# AP.net
KiCad netlist of a schematic drawn in Altium Designer
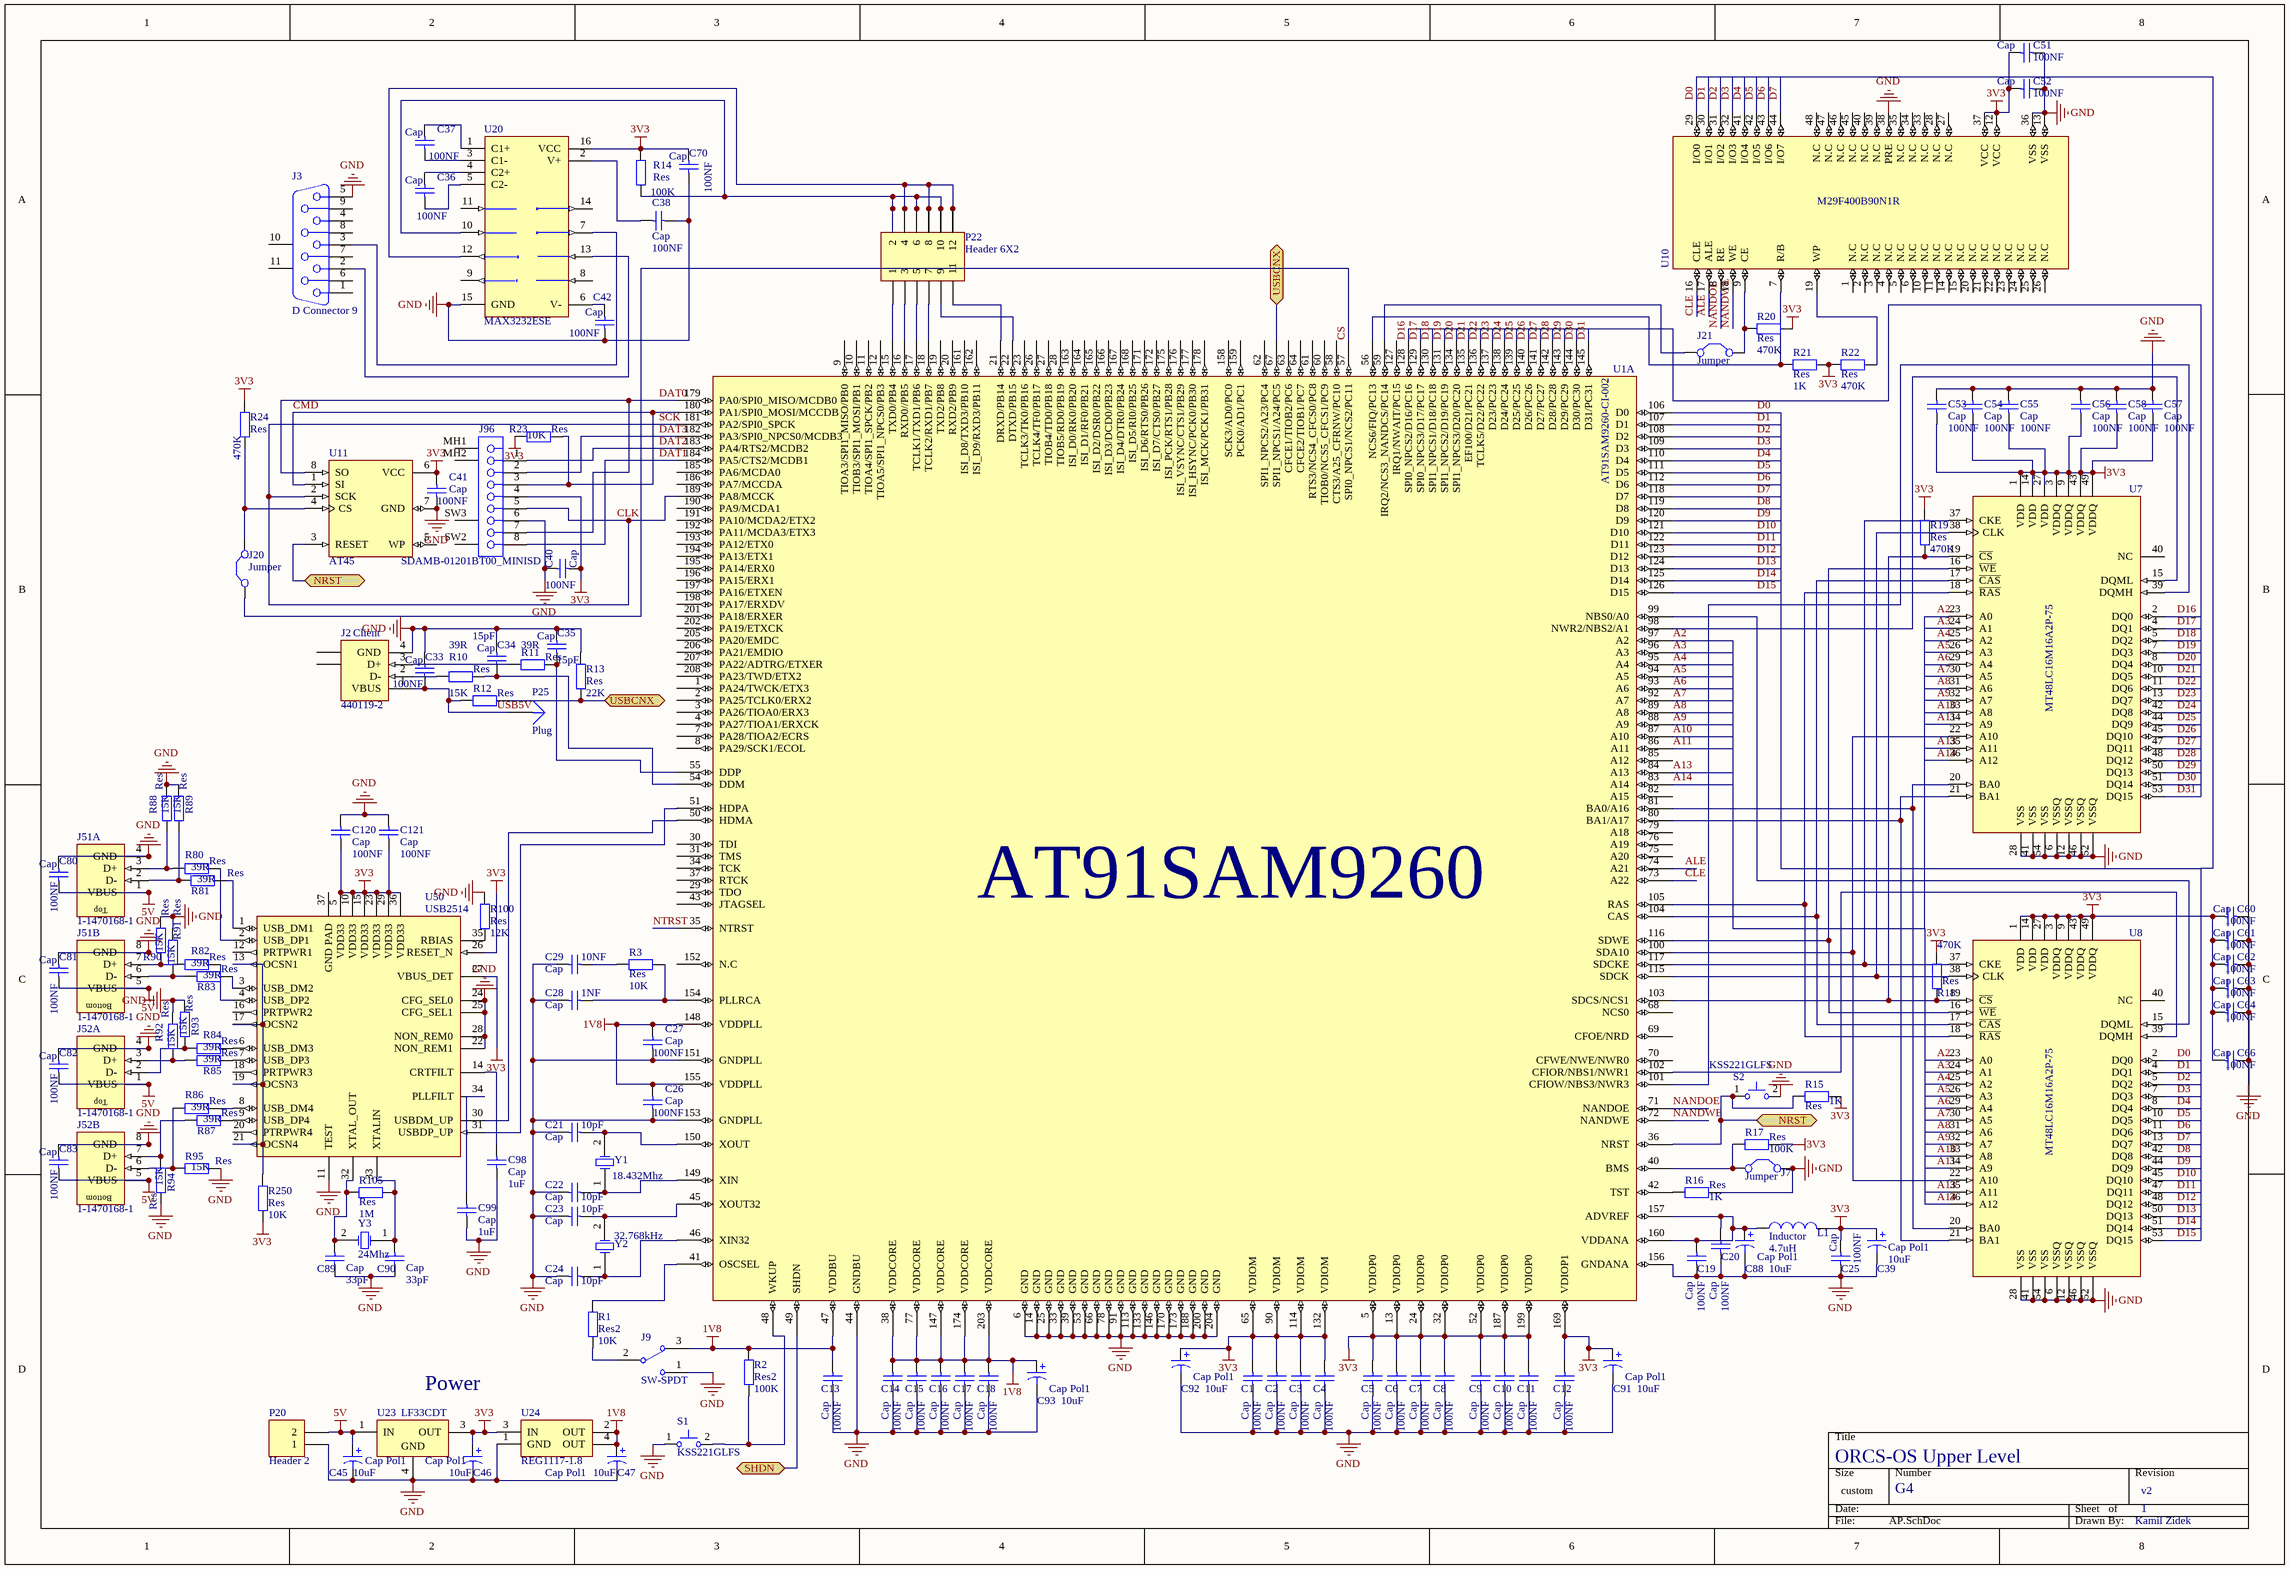
[diagram p0: AP.SchDoc]

(export (version "E")
  (design (tool "Eeschema 10.0.6"))
  (components
    (comp (ref "C1")
      (value "Cap")
      (footprint "C0805")
      (description "Capacitor (Semiconductor SIM Model)")
      (fields (field (name "ALTIUM_VALUE") "100NF") (field (name "PUBLISHER") "Altium Limited"))
      (libsource (lib "Miscellaneous Devices") (part "Cap Semi"))
    )
    (comp (ref "C2")
      (value "Cap")
      (footprint "C0805")
      (description "Capacitor (Semiconductor SIM Model)")
      (fields (field (name "ALTIUM_VALUE") "100NF") (field (name "PUBLISHER") "Altium Limited"))
      (libsource (lib "Miscellaneous Devices") (part "Cap Semi"))
    )
    (comp (ref "C3")
      (value "Cap")
      (footprint "C0805")
      (description "Capacitor (Semiconductor SIM Model)")
      (fields (field (name "ALTIUM_VALUE") "100NF") (field (name "PUBLISHER") "Altium Limited"))
      (libsource (lib "Miscellaneous Devices") (part "Cap Semi"))
    )
    (comp (ref "C4")
      (value "Cap")
      (footprint "C0805")
      (description "Capacitor (Semiconductor SIM Model)")
      (fields (field (name "ALTIUM_VALUE") "100NF") (field (name "PUBLISHER") "Altium Limited"))
      (libsource (lib "Miscellaneous Devices") (part "Cap Semi"))
    )
    (comp (ref "C5")
      (value "Cap")
      (footprint "C0805")
      (description "Capacitor (Semiconductor SIM Model)")
      (fields (field (name "ALTIUM_VALUE") "100NF") (field (name "PUBLISHER") "Altium Limited"))
      (libsource (lib "Miscellaneous Devices") (part "Cap Semi"))
    )
    (comp (ref "C6")
      (value "Cap")
      (footprint "C0805")
      (description "Capacitor (Semiconductor SIM Model)")
      (fields (field (name "ALTIUM_VALUE") "100NF") (field (name "PUBLISHER") "Altium Limited"))
      (libsource (lib "Miscellaneous Devices") (part "Cap Semi"))
    )
    (comp (ref "C7")
      (value "Cap")
      (footprint "C0805")
      (description "Capacitor (Semiconductor SIM Model)")
      (fields (field (name "ALTIUM_VALUE") "100NF") (field (name "PUBLISHER") "Altium Limited"))
      (libsource (lib "Miscellaneous Devices") (part "Cap Semi"))
    )
    (comp (ref "C8")
      (value "Cap")
      (footprint "C0805")
      (description "Capacitor (Semiconductor SIM Model)")
      (fields (field (name "ALTIUM_VALUE") "100NF") (field (name "PUBLISHER") "Altium Limited"))
      (libsource (lib "Miscellaneous Devices") (part "Cap Semi"))
    )
    (comp (ref "C9")
      (value "Cap")
      (footprint "C0805")
      (description "Capacitor (Semiconductor SIM Model)")
      (fields (field (name "ALTIUM_VALUE") "100NF") (field (name "PUBLISHER") "Altium Limited"))
      (libsource (lib "Miscellaneous Devices") (part "Cap Semi"))
    )
    (comp (ref "C10")
      (value "Cap")
      (footprint "C0805")
      (description "Capacitor (Semiconductor SIM Model)")
      (fields (field (name "ALTIUM_VALUE") "100NF") (field (name "PUBLISHER") "Altium Limited"))
      (libsource (lib "Miscellaneous Devices") (part "Cap Semi"))
    )
    (comp (ref "C11")
      (value "Cap")
      (footprint "C0805")
      (description "Capacitor (Semiconductor SIM Model)")
      (fields (field (name "ALTIUM_VALUE") "100NF") (field (name "PUBLISHER") "Altium Limited"))
      (libsource (lib "Miscellaneous Devices") (part "Cap Semi"))
    )
    (comp (ref "C12")
      (value "Cap")
      (footprint "C0805")
      (description "Capacitor (Semiconductor SIM Model)")
      (fields (field (name "ALTIUM_VALUE") "100NF") (field (name "PUBLISHER") "Altium Limited"))
      (libsource (lib "Miscellaneous Devices") (part "Cap Semi"))
    )
    (comp (ref "C13")
      (value "Cap")
      (footprint "C0805")
      (description "Capacitor (Semiconductor SIM Model)")
      (fields (field (name "ALTIUM_VALUE") "100NF") (field (name "PUBLISHER") "Altium Limited"))
      (libsource (lib "Miscellaneous Devices") (part "Cap Semi"))
    )
    (comp (ref "C14")
      (value "Cap")
      (footprint "C0805")
      (description "Capacitor (Semiconductor SIM Model)")
      (fields (field (name "ALTIUM_VALUE") "100NF") (field (name "PUBLISHER") "Altium Limited"))
      (libsource (lib "Miscellaneous Devices") (part "Cap Semi"))
    )
    (comp (ref "C15")
      (value "Cap")
      (footprint "C0805")
      (description "Capacitor (Semiconductor SIM Model)")
      (fields (field (name "ALTIUM_VALUE") "100NF") (field (name "PUBLISHER") "Altium Limited"))
      (libsource (lib "Miscellaneous Devices") (part "Cap Semi"))
    )
    (comp (ref "C16")
      (value "Cap")
      (footprint "C0805")
      (description "Capacitor (Semiconductor SIM Model)")
      (fields (field (name "ALTIUM_VALUE") "100NF") (field (name "PUBLISHER") "Altium Limited"))
      (libsource (lib "Miscellaneous Devices") (part "Cap Semi"))
    )
    (comp (ref "C17")
      (value "Cap")
      (footprint "C0805")
      (description "Capacitor (Semiconductor SIM Model)")
      (fields (field (name "ALTIUM_VALUE") "100NF") (field (name "PUBLISHER") "Altium Limited"))
      (libsource (lib "Miscellaneous Devices") (part "Cap Semi"))
    )
    (comp (ref "C18")
      (value "Cap")
      (footprint "C0805")
      (description "Capacitor (Semiconductor SIM Model)")
      (fields (field (name "ALTIUM_VALUE") "100NF") (field (name "PUBLISHER") "Altium Limited"))
      (libsource (lib "Miscellaneous Devices") (part "Cap Semi"))
    )
    (comp (ref "C19")
      (value "Cap")
      (footprint "C0805")
      (description "Capacitor (Semiconductor SIM Model)")
      (fields (field (name "ALTIUM_VALUE") "100NF") (field (name "PUBLISHER") "Altium Limited"))
      (libsource (lib "Miscellaneous Devices") (part "Cap Semi"))
    )
    (comp (ref "C20")
      (value "Cap")
      (footprint "C0805")
      (description "Capacitor (Semiconductor SIM Model)")
      (fields (field (name "ALTIUM_VALUE") "100NF") (field (name "PUBLISHER") "Altium Limited"))
      (libsource (lib "Miscellaneous Devices") (part "Cap Semi"))
    )
    (comp (ref "C21")
      (value "Cap")
      (footprint "C0805")
      (description "Capacitor (Semiconductor SIM Model)")
      (fields (field (name "ALTIUM_VALUE") "10pF") (field (name "PUBLISHER") "Altium Limited"))
      (libsource (lib "Miscellaneous Devices") (part "Cap Semi"))
    )
    (comp (ref "C22")
      (value "Cap")
      (footprint "C0805")
      (description "Capacitor (Semiconductor SIM Model)")
      (fields (field (name "ALTIUM_VALUE") "10pF") (field (name "PUBLISHER") "Altium Limited"))
      (libsource (lib "Miscellaneous Devices") (part "Cap Semi"))
    )
    (comp (ref "C23")
      (value "Cap")
      (footprint "C0805")
      (description "Capacitor (Semiconductor SIM Model)")
      (fields (field (name "ALTIUM_VALUE") "10pF") (field (name "PUBLISHER") "Altium Limited"))
      (libsource (lib "Miscellaneous Devices") (part "Cap Semi"))
    )
    (comp (ref "C24")
      (value "Cap")
      (footprint "C0805")
      (description "Capacitor (Semiconductor SIM Model)")
      (fields (field (name "ALTIUM_VALUE") "10pF") (field (name "PUBLISHER") "Altium Limited"))
      (libsource (lib "Miscellaneous Devices") (part "Cap Semi"))
    )
    (comp (ref "C25")
      (value "Cap")
      (footprint "C0805")
      (description "Capacitor (Semiconductor SIM Model)")
      (fields (field (name "ALTIUM_VALUE") "100NF") (field (name "PUBLISHER") "Altium Limited"))
      (libsource (lib "Miscellaneous Devices") (part "Cap Semi"))
    )
    (comp (ref "C26")
      (value "Cap")
      (footprint "C0805")
      (description "Capacitor (Semiconductor SIM Model)")
      (fields (field (name "ALTIUM_VALUE") "100NF") (field (name "PUBLISHER") "Altium Limited"))
      (libsource (lib "Miscellaneous Devices") (part "Cap Semi"))
    )
    (comp (ref "C27")
      (value "Cap")
      (footprint "C0805")
      (description "Capacitor (Semiconductor SIM Model)")
      (fields (field (name "ALTIUM_VALUE") "100NF") (field (name "PUBLISHER") "Altium Limited"))
      (libsource (lib "Miscellaneous Devices") (part "Cap Semi"))
    )
    (comp (ref "C28")
      (value "Cap")
      (footprint "C0805")
      (description "Capacitor (Semiconductor SIM Model)")
      (fields (field (name "ALTIUM_VALUE") "1NF") (field (name "PUBLISHER") "Altium Limited"))
      (libsource (lib "Miscellaneous Devices") (part "Cap Semi"))
    )
    (comp (ref "C29")
      (value "Cap")
      (footprint "C0805")
      (description "Capacitor (Semiconductor SIM Model)")
      (fields (field (name "ALTIUM_VALUE") "10NF") (field (name "PUBLISHER") "Altium Limited"))
      (libsource (lib "Miscellaneous Devices") (part "Cap Semi"))
    )
    (comp (ref "C33")
      (value "Cap")
      (footprint "C0805")
      (description "Capacitor (Semiconductor SIM Model)")
      (fields (field (name "ALTIUM_VALUE") "100NF") (field (name "PUBLISHER") "Altium Limited"))
      (libsource (lib "Miscellaneous Devices") (part "Cap Semi"))
    )
    (comp (ref "C34")
      (value "Cap")
      (footprint "C0805")
      (description "Capacitor (Semiconductor SIM Model)")
      (fields (field (name "ALTIUM_VALUE") "15pF") (field (name "PUBLISHER") "Altium Limited"))
      (libsource (lib "Miscellaneous Devices") (part "Cap Semi"))
    )
    (comp (ref "C35")
      (value "Cap")
      (footprint "C0805")
      (description "Capacitor (Semiconductor SIM Model)")
      (fields (field (name "ALTIUM_VALUE") "15pF") (field (name "PUBLISHER") "Altium Limited"))
      (libsource (lib "Miscellaneous Devices") (part "Cap Semi"))
    )
    (comp (ref "C36")
      (value "Cap")
      (footprint "C0805")
      (description "Capacitor (Semiconductor SIM Model)")
      (fields (field (name "ALTIUM_VALUE") "100NF") (field (name "PUBLISHER") "Altium Limited"))
      (libsource (lib "Miscellaneous Devices") (part "Cap Semi"))
    )
    (comp (ref "C37")
      (value "Cap")
      (footprint "C0805")
      (description "Capacitor (Semiconductor SIM Model)")
      (fields (field (name "ALTIUM_VALUE") "100NF") (field (name "PUBLISHER") "Altium Limited"))
      (libsource (lib "Miscellaneous Devices") (part "Cap Semi"))
    )
    (comp (ref "C38")
      (value "Cap")
      (footprint "C0805")
      (description "Capacitor (Semiconductor SIM Model)")
      (fields (field (name "ALTIUM_VALUE") "100NF") (field (name "PUBLISHER") "Altium Limited"))
      (libsource (lib "Miscellaneous Devices") (part "Cap Semi"))
    )
    (comp (ref "C39")
      (value "Cap Pol1")
      (footprint "Miscellaneous Devices:A")
      (description "Polarized Capacitor (Radial)")
      (fields (field (name "ALTIUM_VALUE") "10uF") (field (name "PUBLISHER") "Altium Limited"))
      (libsource (lib "Miscellaneous Devices") (part "Cap Pol1"))
    )
    (comp (ref "C40")
      (value "Cap")
      (footprint "C0805")
      (description "Capacitor (Semiconductor SIM Model)")
      (fields (field (name "ALTIUM_VALUE") "100NF") (field (name "PUBLISHER") "Altium Limited"))
      (libsource (lib "Miscellaneous Devices") (part "Cap Semi"))
    )
    (comp (ref "C41")
      (value "Cap")
      (footprint "C0805")
      (description "Capacitor (Semiconductor SIM Model)")
      (fields (field (name "ALTIUM_VALUE") "100NF") (field (name "PUBLISHER") "Altium Limited"))
      (libsource (lib "Miscellaneous Devices") (part "Cap Semi"))
    )
    (comp (ref "C42")
      (value "Cap")
      (footprint "C0805")
      (description "Capacitor (Semiconductor SIM Model)")
      (fields (field (name "ALTIUM_VALUE") "100NF") (field (name "PUBLISHER") "Altium Limited"))
      (libsource (lib "Miscellaneous Devices") (part "Cap Semi"))
    )
    (comp (ref "C45")
      (value "Cap Pol1")
      (footprint "Miscellaneous Devices:A")
      (description "Polarized Capacitor (Radial)")
      (fields (field (name "ALTIUM_VALUE") "10uF") (field (name "PUBLISHER") "Altium Limited"))
      (libsource (lib "Miscellaneous Devices") (part "Cap Pol1"))
    )
    (comp (ref "C46")
      (value "Cap Pol1")
      (footprint "Miscellaneous Devices:A")
      (description "Polarized Capacitor (Radial)")
      (fields (field (name "ALTIUM_VALUE") "10uF") (field (name "PUBLISHER") "Altium Limited"))
      (libsource (lib "Miscellaneous Devices") (part "Cap Pol1"))
    )
    (comp (ref "C47")
      (value "Cap Pol1")
      (footprint "Miscellaneous Devices:A")
      (description "Polarized Capacitor (Radial)")
      (fields (field (name "ALTIUM_VALUE") "10uF") (field (name "PUBLISHER") "Altium Limited"))
      (libsource (lib "Miscellaneous Devices") (part "Cap Pol1"))
    )
    (comp (ref "C51")
      (value "Cap")
      (footprint "C0805")
      (description "Capacitor (Semiconductor SIM Model)")
      (fields (field (name "ALTIUM_VALUE") "100NF") (field (name "PUBLISHER") "Altium Limited"))
      (libsource (lib "Miscellaneous Devices") (part "Cap Semi"))
    )
    (comp (ref "C52")
      (value "Cap")
      (footprint "C0805")
      (description "Capacitor (Semiconductor SIM Model)")
      (fields (field (name "ALTIUM_VALUE") "100NF") (field (name "PUBLISHER") "Altium Limited"))
      (libsource (lib "Miscellaneous Devices") (part "Cap Semi"))
    )
    (comp (ref "C53")
      (value "Cap")
      (footprint "C0805")
      (description "Capacitor (Semiconductor SIM Model)")
      (fields (field (name "ALTIUM_VALUE") "100NF") (field (name "PUBLISHER") "Altium Limited"))
      (libsource (lib "Miscellaneous Devices") (part "Cap Semi"))
    )
    (comp (ref "C54")
      (value "Cap")
      (footprint "C0805")
      (description "Capacitor (Semiconductor SIM Model)")
      (fields (field (name "ALTIUM_VALUE") "100NF") (field (name "PUBLISHER") "Altium Limited"))
      (libsource (lib "Miscellaneous Devices") (part "Cap Semi"))
    )
    (comp (ref "C55")
      (value "Cap")
      (footprint "C0805")
      (description "Capacitor (Semiconductor SIM Model)")
      (fields (field (name "ALTIUM_VALUE") "100NF") (field (name "PUBLISHER") "Altium Limited"))
      (libsource (lib "Miscellaneous Devices") (part "Cap Semi"))
    )
    (comp (ref "C56")
      (value "Cap")
      (footprint "C0805")
      (description "Capacitor (Semiconductor SIM Model)")
      (fields (field (name "ALTIUM_VALUE") "100NF") (field (name "PUBLISHER") "Altium Limited"))
      (libsource (lib "Miscellaneous Devices") (part "Cap Semi"))
    )
    (comp (ref "C57")
      (value "Cap")
      (footprint "C0805")
      (description "Capacitor (Semiconductor SIM Model)")
      (fields (field (name "ALTIUM_VALUE") "100NF") (field (name "PUBLISHER") "Altium Limited"))
      (libsource (lib "Miscellaneous Devices") (part "Cap Semi"))
    )
    (comp (ref "C58")
      (value "Cap")
      (footprint "C0805")
      (description "Capacitor (Semiconductor SIM Model)")
      (fields (field (name "ALTIUM_VALUE") "100NF") (field (name "PUBLISHER") "Altium Limited"))
      (libsource (lib "Miscellaneous Devices") (part "Cap Semi"))
    )
    (comp (ref "C60")
      (value "Cap")
      (footprint "C0805")
      (description "Capacitor (Semiconductor SIM Model)")
      (fields (field (name "ALTIUM_VALUE") "100NF") (field (name "PUBLISHER") "Altium Limited"))
      (libsource (lib "Miscellaneous Devices") (part "Cap Semi"))
    )
    (comp (ref "C61")
      (value "Cap")
      (footprint "C0805")
      (description "Capacitor (Semiconductor SIM Model)")
      (fields (field (name "ALTIUM_VALUE") "100NF") (field (name "PUBLISHER") "Altium Limited"))
      (libsource (lib "Miscellaneous Devices") (part "Cap Semi"))
    )
    (comp (ref "C62")
      (value "Cap")
      (footprint "C0805")
      (description "Capacitor (Semiconductor SIM Model)")
      (fields (field (name "ALTIUM_VALUE") "100NF") (field (name "PUBLISHER") "Altium Limited"))
      (libsource (lib "Miscellaneous Devices") (part "Cap Semi"))
    )
    (comp (ref "C63")
      (value "Cap")
      (footprint "C0805")
      (description "Capacitor (Semiconductor SIM Model)")
      (fields (field (name "ALTIUM_VALUE") "100NF") (field (name "PUBLISHER") "Altium Limited"))
      (libsource (lib "Miscellaneous Devices") (part "Cap Semi"))
    )
    (comp (ref "C64")
      (value "Cap")
      (footprint "C0805")
      (description "Capacitor (Semiconductor SIM Model)")
      (fields (field (name "ALTIUM_VALUE") "100NF") (field (name "PUBLISHER") "Altium Limited"))
      (libsource (lib "Miscellaneous Devices") (part "Cap Semi"))
    )
    (comp (ref "C66")
      (value "Cap")
      (footprint "C0805")
      (description "Capacitor (Semiconductor SIM Model)")
      (fields (field (name "ALTIUM_VALUE") "100NF") (field (name "PUBLISHER") "Altium Limited"))
      (libsource (lib "Miscellaneous Devices") (part "Cap Semi"))
    )
    (comp (ref "C70")
      (value "Cap")
      (footprint "C0805")
      (description "Capacitor (Semiconductor SIM Model)")
      (fields (field (name "ALTIUM_VALUE") "100NF") (field (name "PUBLISHER") "Altium Limited"))
      (libsource (lib "Miscellaneous Devices") (part "Cap Semi"))
    )
    (comp (ref "C80")
      (value "Cap")
      (footprint "C0805")
      (description "Capacitor (Semiconductor SIM Model)")
      (fields (field (name "ALTIUM_VALUE") "100NF") (field (name "PUBLISHER") "Altium Limited"))
      (libsource (lib "Miscellaneous Devices") (part "Cap Semi"))
    )
    (comp (ref "C81")
      (value "Cap")
      (footprint "C0805")
      (description "Capacitor (Semiconductor SIM Model)")
      (fields (field (name "ALTIUM_VALUE") "100NF") (field (name "PUBLISHER") "Altium Limited"))
      (libsource (lib "Miscellaneous Devices") (part "Cap Semi"))
    )
    (comp (ref "C82")
      (value "Cap")
      (footprint "C0805")
      (description "Capacitor (Semiconductor SIM Model)")
      (fields (field (name "ALTIUM_VALUE") "100NF") (field (name "PUBLISHER") "Altium Limited"))
      (libsource (lib "Miscellaneous Devices") (part "Cap Semi"))
    )
    (comp (ref "C83")
      (value "Cap")
      (footprint "C0805")
      (description "Capacitor (Semiconductor SIM Model)")
      (fields (field (name "ALTIUM_VALUE") "100NF") (field (name "PUBLISHER") "Altium Limited"))
      (libsource (lib "Miscellaneous Devices") (part "Cap Semi"))
    )
    (comp (ref "C88")
      (value "Cap Pol1")
      (footprint "Miscellaneous Devices:A")
      (description "Polarized Capacitor (Radial)")
      (fields (field (name "ALTIUM_VALUE") "10uF") (field (name "PUBLISHER") "Altium Limited"))
      (libsource (lib "Miscellaneous Devices") (part "Cap Pol1"))
    )
    (comp (ref "C89")
      (value "Cap")
      (footprint "C0805")
      (description "Capacitor (Semiconductor SIM Model)")
      (fields (field (name "ALTIUM_VALUE") "33pF") (field (name "PUBLISHER") "Altium Limited"))
      (libsource (lib "Miscellaneous Devices") (part "Cap Semi"))
    )
    (comp (ref "C90")
      (value "Cap")
      (footprint "C0805")
      (description "Capacitor (Semiconductor SIM Model)")
      (fields (field (name "ALTIUM_VALUE") "33pF") (field (name "PUBLISHER") "Altium Limited"))
      (libsource (lib "Miscellaneous Devices") (part "Cap Semi"))
    )
    (comp (ref "C91")
      (value "Cap Pol1")
      (footprint "Miscellaneous Devices:A")
      (description "Polarized Capacitor (Radial)")
      (fields (field (name "ALTIUM_VALUE") "10uF") (field (name "PUBLISHER") "Altium Limited"))
      (libsource (lib "Miscellaneous Devices") (part "Cap Pol1"))
    )
    (comp (ref "C92")
      (value "Cap Pol1")
      (footprint "Miscellaneous Devices:A")
      (description "Polarized Capacitor (Radial)")
      (fields (field (name "ALTIUM_VALUE") "10uF") (field (name "PUBLISHER") "Altium Limited"))
      (libsource (lib "Miscellaneous Devices") (part "Cap Pol1"))
    )
    (comp (ref "C93")
      (value "Cap Pol1")
      (footprint "Miscellaneous Devices:A")
      (description "Polarized Capacitor (Radial)")
      (fields (field (name "ALTIUM_VALUE") "10uF") (field (name "PUBLISHER") "Altium Limited"))
      (libsource (lib "Miscellaneous Devices") (part "Cap Pol1"))
    )
    (comp (ref "C98")
      (value "Cap")
      (footprint "C0805")
      (description "Capacitor (Semiconductor SIM Model)")
      (fields (field (name "ALTIUM_VALUE") "1uF") (field (name "PUBLISHER") "Altium Limited"))
      (libsource (lib "Miscellaneous Devices") (part "Cap Semi"))
    )
    (comp (ref "C99")
      (value "Cap")
      (footprint "C0805")
      (description "Capacitor (Semiconductor SIM Model)")
      (fields (field (name "ALTIUM_VALUE") "1uF") (field (name "PUBLISHER") "Altium Limited"))
      (libsource (lib "Miscellaneous Devices") (part "Cap Semi"))
    )
    (comp (ref "C120")
      (value "Cap")
      (footprint "C0805")
      (description "Capacitor (Semiconductor SIM Model)")
      (fields (field (name "ALTIUM_VALUE") "100NF") (field (name "PUBLISHER") "Altium Limited"))
      (libsource (lib "Miscellaneous Devices") (part "Cap Semi"))
    )
    (comp (ref "C121")
      (value "Cap")
      (footprint "C0805")
      (description "Capacitor (Semiconductor SIM Model)")
      (fields (field (name "ALTIUM_VALUE") "100NF") (field (name "PUBLISHER") "Altium Limited"))
      (libsource (lib "Miscellaneous Devices") (part "Cap Semi"))
    )
    (comp (ref "J2")
      (value "440119-2")
      (footprint "440247")
      (description "USB 1.1, Right Angle, Thru-Hole, B Type, Receptacle, 4 Position, Black")
      (fields (field (name "PUBLISHER") "Altium Limited"))
      (libsource (lib "AMP Serial Bus USB") (part "440119-2"))
    )
    (comp (ref "J3")
      (value "D Connector 9")
      (footprint "DSUB1.385-2H9")
      (description "Receptacle Assembly, 9 Position, Right Angle")
      (fields (field (name "PUBLISHER") "Altium Limited"))
      (libsource (lib "Miscellaneous Connectors") (part "D Connector 9"))
    )
    (comp (ref "J7")
      (value "Jumper")
      (footprint "RAD-0.2")
      (description "Jumper Wire")
      (fields (field (name "PUBLISHER") "Altium Limited"))
      (libsource (lib "Miscellaneous Devices") (part "Jumper"))
    )
    (comp (ref "J9")
      (value "SW-SPDT")
      (footprint "TL36WW15050")
      (description "SPDT Subminiature Toggle Switch, Right Angle Mounting, Vertical Actuation")
      (fields (field (name "PUBLISHER") "Altium Limited"))
      (libsource (lib "Miscellaneous Devices") (part "SW-SPDT"))
    )
    (comp (ref "J20")
      (value "Jumper")
      (footprint "RAD-0.2")
      (description "Jumper Wire")
      (fields (field (name "PUBLISHER") "Altium Limited"))
      (libsource (lib "Miscellaneous Devices") (part "Jumper"))
    )
    (comp (ref "J21")
      (value "Jumper")
      (footprint "RAD-0.2")
      (description "Jumper Wire")
      (fields (field (name "PUBLISHER") "Altium Limited"))
      (libsource (lib "Miscellaneous Devices") (part "Jumper"))
    )
    (comp (ref "J51")
      (value "1-1470168-1")
      (footprint "1470168")
      (description "USB 1.1, Right Angle, Thru-Hole, A Type, Receptacle, 4x4 Position, Stacked, Black")
      (fields (field (name "PUBLISHER") "Altium Limited"))
      (libsource (lib "AMP Serial Bus USB") (part "1-1470168-1"))
    )
    (comp (ref "J52")
      (value "1-1470168-1")
      (footprint "1470168")
      (description "USB 1.1, Right Angle, Thru-Hole, A Type, Receptacle, 4x4 Position, Stacked, Black")
      (fields (field (name "PUBLISHER") "Altium Limited"))
      (libsource (lib "AMP Serial Bus USB") (part "1-1470168-1"))
    )
    (comp (ref "J96")
      (value "SDAMB-01201BT00_MINISD")
      (footprint "Kingfont Card Secure Digital:SDAMB-012_miniSD")
      (description "Secure Digital Card Connector, Type A without Cover; Surface Mount; 9-Position, 1u\" Au Plating")
      (fields (field (name "PUBLISHER") "Altium Limited"))
      (libsource (lib "Kingfont Secure Digital Card_miniSD") (part "SDAMB-01201BT00_MINISD"))
    )
    (comp (ref "L1")
      (value "Inductor")
      (footprint "0402-A")
      (fields (field (name "ALTIUM_VALUE") "4.7uH") (field (name "PUBLISHER") "Altium Limited"))
      (libsource (lib "Miscellaneous Devices") (part "Inductor"))
    )
    (comp (ref "P20")
      (value "Header 2")
      (footprint "HDR1X2")
      (description "Header, 2-Pin")
      (fields (field (name "PUBLISHER") "Altium Limited"))
      (libsource (lib "Miscellaneous Connectors") (part "Header 2"))
    )
    (comp (ref "P22")
      (value "Header 6X2")
      (footprint "HDR2X6")
      (description "Header, 6-Pin, Dual row")
      (fields (field (name "PUBLISHER") "Altium Limited"))
      (libsource (lib "Miscellaneous Connectors") (part "Header 6X2"))
    )
    (comp (ref "P25")
      (value "Plug")
      (footprint "PIN1")
      (fields (field (name "PUBLISHER") "Altium Limited"))
      (libsource (lib "Miscellaneous Connectors") (part "Plug"))
    )
    (comp (ref "R1")
      (value "Res2")
      (footprint "Miscellaneous Devices:2012[0805]")
      (description "Resistor")
      (fields (field (name "ALTIUM_VALUE") "10K") (field (name "PUBLISHER") "Altium Limited"))
      (libsource (lib "") (part "Res2_2"))
    )
    (comp (ref "R2")
      (value "Res2")
      (footprint "Miscellaneous Devices:2012[0805]")
      (description "Resistor")
      (fields (field (name "ALTIUM_VALUE") "100K") (field (name "PUBLISHER") "Altium Limited"))
      (libsource (lib "") (part "Res2_2"))
    )
    (comp (ref "R3")
      (value "Res")
      (footprint "Miscellaneous Devices:2012[0805]")
      (description "Resistor")
      (fields (field (name "ALTIUM_VALUE") "10K") (field (name "PUBLISHER") "Altium Limited"))
      (libsource (lib "Miscellaneous Devices") (part "Res2"))
    )
    (comp (ref "R10")
      (value "Res")
      (footprint "Miscellaneous Devices:2012[0805]")
      (description "Resistor")
      (fields (field (name "ALTIUM_VALUE") "39R") (field (name "PUBLISHER") "Altium Limited"))
      (libsource (lib "Miscellaneous Devices") (part "Res2"))
    )
    (comp (ref "R11")
      (value "Res")
      (footprint "Miscellaneous Devices:2012[0805]")
      (description "Resistor")
      (fields (field (name "ALTIUM_VALUE") "39R") (field (name "PUBLISHER") "Altium Limited"))
      (libsource (lib "Miscellaneous Devices") (part "Res2"))
    )
    (comp (ref "R12")
      (value "Res")
      (footprint "Miscellaneous Devices:2012[0805]")
      (description "Resistor")
      (fields (field (name "ALTIUM_VALUE") "15K") (field (name "PUBLISHER") "Altium Limited"))
      (libsource (lib "Miscellaneous Devices") (part "Res2"))
    )
    (comp (ref "R13")
      (value "Res")
      (footprint "Miscellaneous Devices:2012[0805]")
      (description "Resistor")
      (fields (field (name "ALTIUM_VALUE") "22K") (field (name "PUBLISHER") "Altium Limited"))
      (libsource (lib "") (part "Res2_2"))
    )
    (comp (ref "R14")
      (value "Res")
      (footprint "Miscellaneous Devices:2012[0805]")
      (description "Resistor")
      (fields (field (name "ALTIUM_VALUE") "100K") (field (name "PUBLISHER") "Altium Limited"))
      (libsource (lib "") (part "Res2_2"))
    )
    (comp (ref "R15")
      (value "Res")
      (footprint "Miscellaneous Devices:2012[0805]")
      (description "Resistor")
      (fields (field (name "ALTIUM_VALUE") "1K") (field (name "PUBLISHER") "Altium Limited"))
      (libsource (lib "Miscellaneous Devices") (part "Res2"))
    )
    (comp (ref "R16")
      (value "Res")
      (footprint "Miscellaneous Devices:2012[0805]")
      (description "Resistor")
      (fields (field (name "ALTIUM_VALUE") "1K") (field (name "PUBLISHER") "Altium Limited"))
      (libsource (lib "Miscellaneous Devices") (part "Res2"))
    )
    (comp (ref "R17")
      (value "Res")
      (footprint "Miscellaneous Devices:2012[0805]")
      (description "Resistor")
      (fields (field (name "ALTIUM_VALUE") "100K") (field (name "PUBLISHER") "Altium Limited"))
      (libsource (lib "Miscellaneous Devices") (part "Res2"))
    )
    (comp (ref "R18")
      (value "Res")
      (footprint "Miscellaneous Devices:2012[0805]")
      (description "Resistor")
      (fields (field (name "ALTIUM_VALUE") "470K") (field (name "PUBLISHER") "Altium Limited"))
      (libsource (lib "") (part "Res2_1"))
    )
    (comp (ref "R19")
      (value "Res")
      (footprint "Miscellaneous Devices:2012[0805]")
      (description "Resistor")
      (fields (field (name "ALTIUM_VALUE") "470K") (field (name "PUBLISHER") "Altium Limited"))
      (libsource (lib "") (part "Res2_1"))
    )
    (comp (ref "R20")
      (value "Res")
      (footprint "Miscellaneous Devices:2012[0805]")
      (description "Resistor")
      (fields (field (name "ALTIUM_VALUE") "470K") (field (name "PUBLISHER") "Altium Limited"))
      (libsource (lib "") (part "Res2_3"))
    )
    (comp (ref "R21")
      (value "Res")
      (footprint "Miscellaneous Devices:2012[0805]")
      (description "Resistor")
      (fields (field (name "ALTIUM_VALUE") "1K") (field (name "PUBLISHER") "Altium Limited"))
      (libsource (lib "") (part "Res2_3"))
    )
    (comp (ref "R22")
      (value "Res")
      (footprint "Miscellaneous Devices:2012[0805]")
      (description "Resistor")
      (fields (field (name "ALTIUM_VALUE") "470K") (field (name "PUBLISHER") "Altium Limited"))
      (libsource (lib "") (part "Res2_3"))
    )
    (comp (ref "R23")
      (value "Res")
      (footprint "Miscellaneous Devices:2012[0805]")
      (description "Resistor")
      (fields (field (name "ALTIUM_VALUE") "10K") (field (name "PUBLISHER") "Altium Limited"))
      (libsource (lib "Miscellaneous Devices") (part "Res2"))
    )
    (comp (ref "R24")
      (value "Res")
      (footprint "Miscellaneous Devices:2012[0805]")
      (description "Resistor")
      (fields (field (name "ALTIUM_VALUE") "470K") (field (name "PUBLISHER") "Altium Limited"))
      (libsource (lib "") (part "Res2_1"))
    )
    (comp (ref "R80")
      (value "Res")
      (footprint "Miscellaneous Devices:2012[0805]")
      (description "Resistor")
      (fields (field (name "ALTIUM_VALUE") "39R") (field (name "PUBLISHER") "Altium Limited"))
      (libsource (lib "Miscellaneous Devices") (part "Res2"))
    )
    (comp (ref "R81")
      (value "Res")
      (footprint "Miscellaneous Devices:2012[0805]")
      (description "Resistor")
      (fields (field (name "ALTIUM_VALUE") "39R") (field (name "PUBLISHER") "Altium Limited"))
      (libsource (lib "Miscellaneous Devices") (part "Res2"))
    )
    (comp (ref "R82")
      (value "Res")
      (footprint "Miscellaneous Devices:2012[0805]")
      (description "Resistor")
      (fields (field (name "ALTIUM_VALUE") "39R") (field (name "PUBLISHER") "Altium Limited"))
      (libsource (lib "Miscellaneous Devices") (part "Res2"))
    )
    (comp (ref "R83")
      (value "Res")
      (footprint "Miscellaneous Devices:2012[0805]")
      (description "Resistor")
      (fields (field (name "ALTIUM_VALUE") "39R") (field (name "PUBLISHER") "Altium Limited"))
      (libsource (lib "Miscellaneous Devices") (part "Res2"))
    )
    (comp (ref "R84")
      (value "Res")
      (footprint "Miscellaneous Devices:2012[0805]")
      (description "Resistor")
      (fields (field (name "ALTIUM_VALUE") "39R") (field (name "PUBLISHER") "Altium Limited"))
      (libsource (lib "Miscellaneous Devices") (part "Res2"))
    )
    (comp (ref "R85")
      (value "Res")
      (footprint "Miscellaneous Devices:2012[0805]")
      (description "Resistor")
      (fields (field (name "ALTIUM_VALUE") "39R") (field (name "PUBLISHER") "Altium Limited"))
      (libsource (lib "Miscellaneous Devices") (part "Res2"))
    )
    (comp (ref "R86")
      (value "Res")
      (footprint "Miscellaneous Devices:2012[0805]")
      (description "Resistor")
      (fields (field (name "ALTIUM_VALUE") "39R") (field (name "PUBLISHER") "Altium Limited"))
      (libsource (lib "Miscellaneous Devices") (part "Res2"))
    )
    (comp (ref "R87")
      (value "Res")
      (footprint "Miscellaneous Devices:2012[0805]")
      (description "Resistor")
      (fields (field (name "ALTIUM_VALUE") "39R") (field (name "PUBLISHER") "Altium Limited"))
      (libsource (lib "Miscellaneous Devices") (part "Res2"))
    )
    (comp (ref "R88")
      (value "Res")
      (footprint "Miscellaneous Devices:2012[0805]")
      (description "Resistor")
      (fields (field (name "ALTIUM_VALUE") "15K") (field (name "PUBLISHER") "Altium Limited"))
      (libsource (lib "") (part "Res2_2"))
    )
    (comp (ref "R89")
      (value "Res")
      (footprint "Miscellaneous Devices:2012[0805]")
      (description "Resistor")
      (fields (field (name "ALTIUM_VALUE") "15K") (field (name "PUBLISHER") "Altium Limited"))
      (libsource (lib "") (part "Res2_1"))
    )
    (comp (ref "R90")
      (value "Res")
      (footprint "Miscellaneous Devices:2012[0805]")
      (description "Resistor")
      (fields (field (name "ALTIUM_VALUE") "15K") (field (name "PUBLISHER") "Altium Limited"))
      (libsource (lib "") (part "Res2_2"))
    )
    (comp (ref "R91")
      (value "Res")
      (footprint "Miscellaneous Devices:2012[0805]")
      (description "Resistor")
      (fields (field (name "ALTIUM_VALUE") "15K") (field (name "PUBLISHER") "Altium Limited"))
      (libsource (lib "") (part "Res2_2"))
    )
    (comp (ref "R92")
      (value "Res")
      (footprint "Miscellaneous Devices:2012[0805]")
      (description "Resistor")
      (fields (field (name "ALTIUM_VALUE") "15K") (field (name "PUBLISHER") "Altium Limited"))
      (libsource (lib "") (part "Res2_2"))
    )
    (comp (ref "R93")
      (value "Res")
      (footprint "Miscellaneous Devices:2012[0805]")
      (description "Resistor")
      (fields (field (name "ALTIUM_VALUE") "15K") (field (name "PUBLISHER") "Altium Limited"))
      (libsource (lib "") (part "Res2_2"))
    )
    (comp (ref "R94")
      (value "Res")
      (footprint "Miscellaneous Devices:2012[0805]")
      (description "Resistor")
      (fields (field (name "ALTIUM_VALUE") "15K") (field (name "PUBLISHER") "Altium Limited"))
      (libsource (lib "") (part "Res2_2"))
    )
    (comp (ref "R95")
      (value "Res")
      (footprint "Miscellaneous Devices:2012[0805]")
      (description "Resistor")
      (fields (field (name "ALTIUM_VALUE") "15K") (field (name "PUBLISHER") "Altium Limited"))
      (libsource (lib "Miscellaneous Devices") (part "Res2"))
    )
    (comp (ref "R100")
      (value "Res")
      (footprint "Miscellaneous Devices:2012[0805]")
      (description "Resistor")
      (fields (field (name "ALTIUM_VALUE") "12K") (field (name "PUBLISHER") "Altium Limited"))
      (libsource (lib "") (part "Res2_2"))
    )
    (comp (ref "R105")
      (value "Res")
      (footprint "Miscellaneous Devices:2012[0805]")
      (description "Resistor")
      (fields (field (name "ALTIUM_VALUE") "1M") (field (name "PUBLISHER") "Altium Limited"))
      (libsource (lib "Miscellaneous Devices") (part "Res2"))
    )
    (comp (ref "R250")
      (value "Res")
      (footprint "Miscellaneous Devices:2012[0805]")
      (description "Resistor")
      (fields (field (name "ALTIUM_VALUE") "10K") (field (name "PUBLISHER") "Altium Limited"))
      (libsource (lib "") (part "Res2_1"))
    )
    (comp (ref "S1")
      (value "KSS221GLFS")
      (footprint "KSS-2G")
      (fields (field (name "PUBLISHER") "Altium Limited"))
      (libsource (lib "CK Switch") (part "KSS221GLFS"))
    )
    (comp (ref "S2")
      (value "KSS221GLFS")
      (footprint "KSS-2G")
      (fields (field (name "PUBLISHER") "Altium Limited"))
      (libsource (lib "CK Switch") (part "KSS221GLFS"))
    )
    (comp (ref "U1")
      (value "AT91SAM9260-CI-002")
      (footprint "QFP208_M")
      (fields (field (name "PUBLISHER") "Altium Limited"))
      (libsource (lib "Atmel Microcontroller 16-Bit ARM2_at91sam9260") (part "AT91RM9200-CI-002"))
    )
    (comp (ref "U7")
      (value "MT48LC16M16A2P-75")
      (footprint "TSOP2-54_L")
      (description "256Mb Synchronous High-Speed CMOS DRAM, 16Mb x 16Bit x 4 Banks, 54-Pin TSOP Pb-free, Commercial")
      (fields (field (name "PUBLISHER") "Altium Limited"))
      (libsource (lib "Micron Memory Dynamic RAM") (part "MT48LC16M16A2P-75"))
    )
    (comp (ref "U8")
      (value "MT48LC16M16A2P-75")
      (footprint "TSOP2-54_L")
      (description "256Mb Synchronous High-Speed CMOS DRAM, 16Mb x 16Bit x 4 Banks, 54-Pin TSOP Pb-free, Commercial")
      (fields (field (name "PUBLISHER") "Altium Limited"))
      (libsource (lib "Micron Memory Dynamic RAM") (part "MT48LC16M16A2P-75"))
    )
    (comp (ref "U10")
      (value "M29F400B90N1R")
      (footprint "TSOP48")
      (description "4 Mbit (512Kb x8 or 256Kb x16, Boot Block) Single Supply Flash Memory")
      (fields (field (name "PUBLISHER") "Altium Limited"))
      (libsource (lib "ST Memory EEPROM Flash") (part "M29F400B90N1R"))
    )
    (comp (ref "U11")
      (value "AT45")
      (footprint "SO8W_N")
      (description "16Mbit Serial I²C Bus SERIAL FLASH")
      (fields (field (name "PUBLISHER") "Altium Limited"))
      (libsource (lib "ST Memory EEPROM Serial") (part "AT45"))
    )
    (comp (ref "U20")
      (value "MAX3232ESE")
      (footprint "NSO16_N")
      (description "3.0V TO 5.5V, Low-Power, up to 1Mbps, True RS-232 Transceiver Using Four 0.1µF External Capacitor")
      (fields (field (name "PUBLISHER") "Altium Limited"))
      (libsource (lib "Maxim Communication Transceiver") (part "MAX3232ESE"))
    )
    (comp (ref "U23")
      (value "LF33CDT")
      (footprint "TO-252")
      (description "500mA, Very Low Drop (0.45V) Voltage Regulator")
      (fields (field (name "PUBLISHER") "Altium Limited"))
      (libsource (lib "ST Power Mgt Voltage Regulator") (part "LF33CDT"))
    )
    (comp (ref "U24")
      (value "REG1117-1.8")
      (footprint "ZZ311")
      (description "800mA and 1A Low Dropout Positive Regulator 2.85V, 3.3V, 5V, and Adjustable")
      (fields (field (name "PUBLISHER") "Altium Limited"))
      (libsource (lib "BB Power Mgt Voltage Regulator") (part "REG1117-2.85"))
    )
    (comp (ref "U50")
      (value "USB2514")
      (footprint "FTDI Communication UART:QFN36_L")
      (description "USB UART Asynchronous Serial Data Transfer Chip, QFN32, Pb-Free")
      (fields (field (name "PUBLISHER") "Altium Limited"))
      (libsource (lib "FTDI Communication UART_USB_HUB") (part "USB2514"))
    )
    (comp (ref "Y1")
      (value "18.432Mhz")
      (footprint "HC-49U")
      (description "Crystal Oscillator")
      (fields (field (name "PUBLISHER") "Altium Limited"))
      (libsource (lib "ECS Crystal Oscillator") (part "ECS-10-13-1"))
    )
    (comp (ref "Y2")
      (value "32.768kHz")
      (footprint "R38")
      (description "Crystal Oscillator")
      (fields (field (name "PUBLISHER") "Altium Limited"))
      (libsource (lib "ECS Crystal Oscillator") (part "ECS-10-13-1"))
    )
    (comp (ref "Y3")
      (value "24Mhz")
      (footprint "HC-49U")
      (description "Crystal Oscillator")
      (fields (field (name "PUBLISHER") "Altium Limited"))
      (libsource (lib "ECS Crystal Oscillator") (part "ECS-10-13-1"))
    )
  )
  (nets
    (net (code "1") (name "/A2") (class "Default")
      (node (ref "U1") (pin "97") (pinfunction "A2_97") (pintype "bidirectional"))
      (node (ref "U7") (pin "23") (pinfunction "A0_23") (pintype "input"))
      (node (ref "U8") (pin "23") (pinfunction "A0_23") (pintype "input"))
    )
    (net (code "2") (name "/A3") (class "Default")
      (node (ref "U1") (pin "96") (pinfunction "A3_96") (pintype "bidirectional"))
      (node (ref "U7") (pin "24") (pinfunction "A1_24") (pintype "input"))
      (node (ref "U8") (pin "24") (pinfunction "A1_24") (pintype "input"))
    )
    (net (code "3") (name "/A4") (class "Default")
      (node (ref "U1") (pin "95") (pinfunction "A4_95") (pintype "bidirectional"))
      (node (ref "U7") (pin "25") (pinfunction "A2_25") (pintype "input"))
      (node (ref "U8") (pin "25") (pinfunction "A2_25") (pintype "input"))
    )
    (net (code "4") (name "/A5") (class "Default")
      (node (ref "U1") (pin "94") (pinfunction "A5_94") (pintype "bidirectional"))
      (node (ref "U7") (pin "26") (pinfunction "A3_26") (pintype "input"))
      (node (ref "U8") (pin "26") (pinfunction "A3_26") (pintype "input"))
    )
    (net (code "5") (name "/A6") (class "Default")
      (node (ref "U1") (pin "93") (pinfunction "A6_93") (pintype "bidirectional"))
      (node (ref "U7") (pin "29") (pinfunction "A4_29") (pintype "input"))
      (node (ref "U8") (pin "29") (pinfunction "A4_29") (pintype "input"))
    )
    (net (code "6") (name "/A7") (class "Default")
      (node (ref "U1") (pin "92") (pinfunction "A7_92") (pintype "bidirectional"))
      (node (ref "U7") (pin "30") (pinfunction "A5_30") (pintype "input"))
      (node (ref "U8") (pin "30") (pinfunction "A5_30") (pintype "input"))
    )
    (net (code "7") (name "/A8") (class "Default")
      (node (ref "U1") (pin "89") (pinfunction "A8_89") (pintype "bidirectional"))
      (node (ref "U7") (pin "31") (pinfunction "A6_31") (pintype "input"))
      (node (ref "U8") (pin "31") (pinfunction "A6_31") (pintype "input"))
    )
    (net (code "8") (name "/A9") (class "Default")
      (node (ref "U1") (pin "88") (pinfunction "A9_88") (pintype "bidirectional"))
      (node (ref "U7") (pin "32") (pinfunction "A7_32") (pintype "input"))
      (node (ref "U8") (pin "32") (pinfunction "A7_32") (pintype "input"))
    )
    (net (code "9") (name "/A10") (class "Default")
      (node (ref "U1") (pin "87") (pinfunction "A10_87") (pintype "bidirectional"))
      (node (ref "U7") (pin "33") (pinfunction "A8_33") (pintype "input"))
      (node (ref "U8") (pin "33") (pinfunction "A8_33") (pintype "input"))
    )
    (net (code "10") (name "/A11") (class "Default")
      (node (ref "U1") (pin "86") (pinfunction "A11_86") (pintype "bidirectional"))
      (node (ref "U7") (pin "34") (pinfunction "A9_34") (pintype "input"))
      (node (ref "U8") (pin "34") (pinfunction "A9_34") (pintype "input"))
    )
    (net (code "11") (name "/A13") (class "Default")
      (node (ref "U1") (pin "84") (pinfunction "A13_84") (pintype "bidirectional"))
      (node (ref "U7") (pin "35") (pinfunction "A11_35") (pintype "input"))
      (node (ref "U8") (pin "35") (pinfunction "A11_35") (pintype "input"))
    )
    (net (code "12") (name "/A14") (class "Default")
      (node (ref "U1") (pin "83") (pinfunction "A14_83") (pintype "bidirectional"))
      (node (ref "U7") (pin "36") (pinfunction "A12_36") (pintype "input"))
      (node (ref "U8") (pin "36") (pinfunction "A12_36") (pintype "input"))
    )
    (net (code "13") (name "/ALE") (class "Default")
      (node (ref "U1") (pin "74") (pinfunction "A21_74") (pintype "bidirectional"))
      (node (ref "U10") (pin "17") (pinfunction "ALE_17") (pintype "bidirectional"))
    )
    (net (code "14") (name "/CLE") (class "Default")
      (node (ref "U1") (pin "73") (pinfunction "A22_73") (pintype "bidirectional"))
      (node (ref "U10") (pin "16") (pinfunction "CLE_16") (pintype "bidirectional"))
    )
    (net (code "15") (name "/CLK") (class "Default")
      (node (ref "J96") (pin "5") (pinfunction "5_5") (pintype "passive"))
      (node (ref "U1") (pin "181") (pinfunction "PA2/SPI0_SPCK_181") (pintype "bidirectional"))
      (node (ref "U1") (pin "189") (pinfunction "PA8/MCCK_189") (pintype "bidirectional"))
      (node (ref "U11") (pin "2") (pinfunction "SCK_2") (pintype "input"))
    )
    (net (code "16") (name "/CMD") (class "Default")
      (node (ref "J96") (pin "3") (pinfunction "3_3") (pintype "passive"))
      (node (ref "R23") (pin "1") (pinfunction "1_1") (pintype "passive"))
      (node (ref "U1") (pin "180") (pinfunction "PA1/SPI0_MOSI/MCCDB_180") (pintype "bidirectional"))
      (node (ref "U11") (pin "1") (pinfunction "SI_1") (pintype "input"))
    )
    (net (code "17") (name "/CS") (class "Default")
      (node (ref "J20") (pin "1") (pinfunction "C1_1") (pintype "passive"))
      (node (ref "U1") (pin "57") (pinfunction "SPI0_NPCS1/NCS2/PC11_57") (pintype "bidirectional"))
    )
    (net (code "18") (name "/D0") (class "Default")
      (node (ref "U1") (pin "106") (pinfunction "D0_106") (pintype "bidirectional"))
      (node (ref "U10") (pin "29") (pinfunction "I/O0_29") (pintype "bidirectional"))
      (node (ref "U8") (pin "2") (pinfunction "DQ0_2") (pintype "bidirectional"))
    )
    (net (code "19") (name "/D1") (class "Default")
      (node (ref "U1") (pin "107") (pinfunction "D1_107") (pintype "bidirectional"))
      (node (ref "U10") (pin "30") (pinfunction "I/O1_30") (pintype "bidirectional"))
      (node (ref "U8") (pin "4") (pinfunction "DQ1_4") (pintype "bidirectional"))
    )
    (net (code "20") (name "/D2") (class "Default")
      (node (ref "U1") (pin "108") (pinfunction "D2_108") (pintype "bidirectional"))
      (node (ref "U10") (pin "31") (pinfunction "I/O2_31") (pintype "bidirectional"))
      (node (ref "U8") (pin "5") (pinfunction "DQ2_5") (pintype "bidirectional"))
    )
    (net (code "21") (name "/D3") (class "Default")
      (node (ref "U1") (pin "109") (pinfunction "D3_109") (pintype "bidirectional"))
      (node (ref "U10") (pin "32") (pinfunction "I/O3_32") (pintype "bidirectional"))
      (node (ref "U8") (pin "7") (pinfunction "DQ3_7") (pintype "bidirectional"))
    )
    (net (code "22") (name "/D4") (class "Default")
      (node (ref "U1") (pin "110") (pinfunction "D4_110") (pintype "bidirectional"))
      (node (ref "U10") (pin "41") (pinfunction "I/O4_41") (pintype "bidirectional"))
      (node (ref "U8") (pin "8") (pinfunction "DQ4_8") (pintype "bidirectional"))
    )
    (net (code "23") (name "/D5") (class "Default")
      (node (ref "U1") (pin "111") (pinfunction "D5_111") (pintype "bidirectional"))
      (node (ref "U10") (pin "42") (pinfunction "I/O5_42") (pintype "bidirectional"))
      (node (ref "U8") (pin "10") (pinfunction "DQ5_10") (pintype "bidirectional"))
    )
    (net (code "24") (name "/D6") (class "Default")
      (node (ref "U1") (pin "112") (pinfunction "D6_112") (pintype "bidirectional"))
      (node (ref "U10") (pin "43") (pinfunction "I/O6_43") (pintype "bidirectional"))
      (node (ref "U8") (pin "11") (pinfunction "DQ6_11") (pintype "bidirectional"))
    )
    (net (code "25") (name "/D7") (class "Default")
      (node (ref "U1") (pin "118") (pinfunction "D7_118") (pintype "bidirectional"))
      (node (ref "U10") (pin "44") (pinfunction "I/O7_44") (pintype "bidirectional"))
      (node (ref "U8") (pin "13") (pinfunction "DQ7_13") (pintype "bidirectional"))
    )
    (net (code "26") (name "/D8") (class "Default")
      (node (ref "U1") (pin "119") (pinfunction "D8_119") (pintype "bidirectional"))
      (node (ref "U8") (pin "42") (pinfunction "DQ8_42") (pintype "bidirectional"))
    )
    (net (code "27") (name "/D9") (class "Default")
      (node (ref "U1") (pin "120") (pinfunction "D9_120") (pintype "bidirectional"))
      (node (ref "U8") (pin "44") (pinfunction "DQ9_44") (pintype "bidirectional"))
    )
    (net (code "28") (name "/D10") (class "Default")
      (node (ref "U1") (pin "121") (pinfunction "D10_121") (pintype "bidirectional"))
      (node (ref "U8") (pin "45") (pinfunction "DQ10_45") (pintype "bidirectional"))
    )
    (net (code "29") (name "/D11") (class "Default")
      (node (ref "U1") (pin "122") (pinfunction "D11_122") (pintype "bidirectional"))
      (node (ref "U8") (pin "47") (pinfunction "DQ11_47") (pintype "bidirectional"))
    )
    (net (code "30") (name "/D12") (class "Default")
      (node (ref "U1") (pin "123") (pinfunction "D12_123") (pintype "bidirectional"))
      (node (ref "U8") (pin "48") (pinfunction "DQ12_48") (pintype "bidirectional"))
    )
    (net (code "31") (name "/D13") (class "Default")
      (node (ref "U1") (pin "124") (pinfunction "D13_124") (pintype "bidirectional"))
      (node (ref "U8") (pin "50") (pinfunction "DQ13_50") (pintype "bidirectional"))
    )
    (net (code "32") (name "/D14") (class "Default")
      (node (ref "U1") (pin "125") (pinfunction "D14_125") (pintype "bidirectional"))
      (node (ref "U8") (pin "51") (pinfunction "DQ14_51") (pintype "bidirectional"))
    )
    (net (code "33") (name "/D15") (class "Default")
      (node (ref "U1") (pin "126") (pinfunction "D15_126") (pintype "bidirectional"))
      (node (ref "U8") (pin "53") (pinfunction "DQ15_53") (pintype "bidirectional"))
    )
    (net (code "34") (name "/D16") (class "Default")
      (node (ref "U1") (pin "128") (pinfunction "SPI0_NPCS2/D16/PC16_128") (pintype "bidirectional"))
      (node (ref "U7") (pin "2") (pinfunction "DQ0_2") (pintype "bidirectional"))
    )
    (net (code "35") (name "/D17") (class "Default")
      (node (ref "U1") (pin "129") (pinfunction "SPI0_NPCS3/D17/PC17_129") (pintype "bidirectional"))
      (node (ref "U7") (pin "4") (pinfunction "DQ1_4") (pintype "bidirectional"))
    )
    (net (code "36") (name "/D18") (class "Default")
      (node (ref "U1") (pin "130") (pinfunction "SPI1_NPCS1/D18/PC18_130") (pintype "bidirectional"))
      (node (ref "U7") (pin "5") (pinfunction "DQ2_5") (pintype "bidirectional"))
    )
    (net (code "37") (name "/D19") (class "Default")
      (node (ref "U1") (pin "131") (pinfunction "SPI1_NPCS2/D19/PC19_131") (pintype "bidirectional"))
      (node (ref "U7") (pin "7") (pinfunction "DQ3_7") (pintype "bidirectional"))
    )
    (net (code "38") (name "/D20") (class "Default")
      (node (ref "U1") (pin "134") (pinfunction "SPI1_NPCS3/D20/PC20_134") (pintype "bidirectional"))
      (node (ref "U7") (pin "8") (pinfunction "DQ4_8") (pintype "bidirectional"))
    )
    (net (code "39") (name "/D21") (class "Default")
      (node (ref "U1") (pin "135") (pinfunction "EF100/D21/PC21_135") (pintype "bidirectional"))
      (node (ref "U7") (pin "10") (pinfunction "DQ5_10") (pintype "bidirectional"))
    )
    (net (code "40") (name "/D22") (class "Default")
      (node (ref "U1") (pin "136") (pinfunction "TCLK5/D22/PC22_136") (pintype "bidirectional"))
      (node (ref "U7") (pin "11") (pinfunction "DQ6_11") (pintype "bidirectional"))
    )
    (net (code "41") (name "/D23") (class "Default")
      (node (ref "U1") (pin "137") (pinfunction "D23/PC23_137") (pintype "bidirectional"))
      (node (ref "U7") (pin "13") (pinfunction "DQ7_13") (pintype "bidirectional"))
    )
    (net (code "42") (name "/D24") (class "Default")
      (node (ref "U1") (pin "138") (pinfunction "D24/PC24_138") (pintype "bidirectional"))
      (node (ref "U7") (pin "42") (pinfunction "DQ8_42") (pintype "bidirectional"))
    )
    (net (code "43") (name "/D25") (class "Default")
      (node (ref "U1") (pin "139") (pinfunction "D25/PC25_139") (pintype "bidirectional"))
      (node (ref "U7") (pin "44") (pinfunction "DQ9_44") (pintype "bidirectional"))
    )
    (net (code "44") (name "/D26") (class "Default")
      (node (ref "U1") (pin "140") (pinfunction "D26/PC26_140") (pintype "bidirectional"))
      (node (ref "U7") (pin "45") (pinfunction "DQ10_45") (pintype "bidirectional"))
    )
    (net (code "45") (name "/D27") (class "Default")
      (node (ref "U1") (pin "141") (pinfunction "D27/PC27_141") (pintype "bidirectional"))
      (node (ref "U7") (pin "47") (pinfunction "DQ11_47") (pintype "bidirectional"))
    )
    (net (code "46") (name "/D28") (class "Default")
      (node (ref "U1") (pin "142") (pinfunction "D28/PC28_142") (pintype "bidirectional"))
      (node (ref "U7") (pin "48") (pinfunction "DQ12_48") (pintype "bidirectional"))
    )
    (net (code "47") (name "/D29") (class "Default")
      (node (ref "U1") (pin "143") (pinfunction "D29/PC29_143") (pintype "bidirectional"))
      (node (ref "U7") (pin "50") (pinfunction "DQ13_50") (pintype "bidirectional"))
    )
    (net (code "48") (name "/D30") (class "Default")
      (node (ref "U1") (pin "144") (pinfunction "D30/PC30_144") (pintype "bidirectional"))
      (node (ref "U7") (pin "51") (pinfunction "DQ14_51") (pintype "bidirectional"))
    )
    (net (code "49") (name "/D31") (class "Default")
      (node (ref "U1") (pin "145") (pinfunction "D31/PC31_145") (pintype "bidirectional"))
      (node (ref "U7") (pin "53") (pinfunction "DQ15_53") (pintype "bidirectional"))
    )
    (net (code "50") (name "/DAT0") (class "Default")
      (node (ref "J96") (pin "7") (pinfunction "7_7") (pintype "passive"))
      (node (ref "U1") (pin "179") (pinfunction "PA0/SPI0_MISO/MCDB0_179") (pintype "bidirectional"))
      (node (ref "U11") (pin "8") (pinfunction "SO_8") (pintype "input"))
    )
    (net (code "51") (name "/DAT1") (class "Default")
      (node (ref "J96") (pin "8") (pinfunction "8_8") (pintype "passive"))
      (node (ref "U1") (pin "184") (pinfunction "PA5/CTS2/MCDB1_184") (pintype "bidirectional"))
    )
    (net (code "52") (name "/DAT2") (class "Default")
      (node (ref "J96") (pin "1") (pinfunction "1_1") (pintype "passive"))
      (node (ref "U1") (pin "183") (pinfunction "PA4/RTS2/MCDB2_183") (pintype "bidirectional"))
    )
    (net (code "53") (name "/DAT3") (class "Default")
      (node (ref "J96") (pin "2") (pinfunction "2_2") (pintype "passive"))
      (node (ref "U1") (pin "182") (pinfunction "PA3/SPI0_NPCS0/MCDB3_182") (pintype "bidirectional"))
    )
    (net (code "54") (name "/NANDOE") (class "Default")
      (node (ref "U1") (pin "71") (pinfunction "NANDOE_71") (pintype "bidirectional"))
      (node (ref "U10") (pin "8") (pinfunction "RE_8") (pintype "bidirectional"))
    )
    (net (code "55") (name "/NANDWE") (class "Default")
      (node (ref "U1") (pin "72") (pinfunction "NANDWE_72") (pintype "bidirectional"))
      (node (ref "U10") (pin "18") (pinfunction "WE_18") (pintype "bidirectional"))
    )
    (net (code "56") (name "/NRST") (class "Default")
      (node (ref "R15") (pin "2") (pinfunction "2_2") (pintype "passive"))
      (node (ref "S2") (pin "1") (pinfunction "1_1") (pintype "passive"))
      (node (ref "U1") (pin "36") (pinfunction "NRST_36") (pintype "bidirectional"))
      (node (ref "U11") (pin "3") (pinfunction "RESET_3") (pintype "input"))
    )
    (net (code "57") (name "/NTRST") (class "Default")
      (node (ref "U1") (pin "35") (pinfunction "NTRST_35") (pintype "bidirectional"))
    )
    (net (code "58") (name "/SHDN") (class "Default")
      (node (ref "U1") (pin "49") (pinfunction "SHDN_49") (pintype "bidirectional"))
    )
    (net (code "59") (name "/USB5V") (class "Default")
      (node (ref "C33") (pin "1") (pinfunction "1_1") (pintype "passive"))
      (node (ref "J2") (pin "1") (pinfunction "VBUS_1") (pintype "power_in"))
      (node (ref "P25") (pin "1") (pinfunction "1_1") (pintype "passive"))
      (node (ref "R12") (pin "2") (pinfunction "2_2") (pintype "passive"))
    )
    (net (code "60") (name "/USBCNX") (class "Default")
      (node (ref "R12") (pin "1") (pinfunction "1_1") (pintype "passive"))
      (node (ref "R13") (pin "1") (pinfunction "1_1") (pintype "passive"))
      (node (ref "U1") (pin "67") (pinfunction "SPI1_NPCS1/A24/PC5_67") (pintype "bidirectional"))
    )
    (net (code "61") (name "1V8") (class "Default")
      (node (ref "C13") (pin "2") (pinfunction "2_2") (pintype "passive"))
      (node (ref "C14") (pin "2") (pinfunction "2_2") (pintype "passive"))
      (node (ref "C15") (pin "2") (pinfunction "2_2") (pintype "passive"))
      (node (ref "C16") (pin "2") (pinfunction "2_2") (pintype "passive"))
      (node (ref "C17") (pin "2") (pinfunction "2_2") (pintype "passive"))
      (node (ref "C18") (pin "2") (pinfunction "2_2") (pintype "passive"))
      (node (ref "C26") (pin "1") (pinfunction "1_1") (pintype "passive"))
      (node (ref "C27") (pin "1") (pinfunction "1_1") (pintype "passive"))
      (node (ref "C47") (pin "1") (pinfunction "1_1") (pintype "passive"))
      (node (ref "C93") (pin "1") (pinfunction "1_1") (pintype "passive"))
      (node (ref "J9") (pin "3") (pinfunction "3_3") (pintype "passive"))
      (node (ref "R2") (pin "2") (pinfunction "2_2") (pintype "passive"))
      (node (ref "U1") (pin "147") (pinfunction "VDDCORE_147") (pintype "bidirectional"))
      (node (ref "U1") (pin "148") (pinfunction "VDDPLL_148") (pintype "bidirectional"))
      (node (ref "U1") (pin "155") (pinfunction "VDDPLL_155") (pintype "bidirectional"))
      (node (ref "U1") (pin "174") (pinfunction "VDDCORE_174") (pintype "bidirectional"))
      (node (ref "U1") (pin "203") (pinfunction "VDDCORE_203") (pintype "bidirectional"))
      (node (ref "U1") (pin "38") (pinfunction "VDDCORE_38") (pintype "bidirectional"))
      (node (ref "U1") (pin "47") (pinfunction "VDDBU_47") (pintype "bidirectional"))
      (node (ref "U1") (pin "77") (pinfunction "VDDCORE_77") (pintype "bidirectional"))
      (node (ref "U24") (pin "2") (pinfunction "OUT_2") (pintype "power_in"))
      (node (ref "U24") (pin "4") (pinfunction "OUT_4") (pintype "power_in"))
    )
    (net (code "62") (name "3V3") (class "Default")
      (node (ref "C1") (pin "2") (pinfunction "2_2") (pintype "passive"))
      (node (ref "C10") (pin "2") (pinfunction "2_2") (pintype "passive"))
      (node (ref "C11") (pin "2") (pinfunction "2_2") (pintype "passive"))
      (node (ref "C12") (pin "2") (pinfunction "2_2") (pintype "passive"))
      (node (ref "C120") (pin "1") (pinfunction "1_1") (pintype "passive"))
      (node (ref "C121") (pin "2") (pinfunction "2_2") (pintype "passive"))
      (node (ref "C2") (pin "2") (pinfunction "2_2") (pintype "passive"))
      (node (ref "C25") (pin "2") (pinfunction "2_2") (pintype "passive"))
      (node (ref "C3") (pin "2") (pinfunction "2_2") (pintype "passive"))
      (node (ref "C39") (pin "1") (pinfunction "1_1") (pintype "passive"))
      (node (ref "C4") (pin "2") (pinfunction "2_2") (pintype "passive"))
      (node (ref "C40") (pin "1") (pinfunction "1_1") (pintype "passive"))
      (node (ref "C41") (pin "1") (pinfunction "1_1") (pintype "passive"))
      (node (ref "C46") (pin "1") (pinfunction "1_1") (pintype "passive"))
      (node (ref "C5") (pin "2") (pinfunction "2_2") (pintype "passive"))
      (node (ref "C51") (pin "2") (pinfunction "2_2") (pintype "passive"))
      (node (ref "C52") (pin "2") (pinfunction "2_2") (pintype "passive"))
      (node (ref "C53") (pin "2") (pinfunction "2_2") (pintype "passive"))
      (node (ref "C54") (pin "2") (pinfunction "2_2") (pintype "passive"))
      (node (ref "C55") (pin "2") (pinfunction "2_2") (pintype "passive"))
      (node (ref "C56") (pin "2") (pinfunction "2_2") (pintype "passive"))
      (node (ref "C57") (pin "2") (pinfunction "2_2") (pintype "passive"))
      (node (ref "C58") (pin "2") (pinfunction "2_2") (pintype "passive"))
      (node (ref "C6") (pin "2") (pinfunction "2_2") (pintype "passive"))
      (node (ref "C60") (pin "1") (pinfunction "1_1") (pintype "passive"))
      (node (ref "C61") (pin "1") (pinfunction "1_1") (pintype "passive"))
      (node (ref "C62") (pin "1") (pinfunction "1_1") (pintype "passive"))
      (node (ref "C63") (pin "1") (pinfunction "1_1") (pintype "passive"))
      (node (ref "C64") (pin "1") (pinfunction "1_1") (pintype "passive"))
      (node (ref "C66") (pin "1") (pinfunction "1_1") (pintype "passive"))
      (node (ref "C7") (pin "2") (pinfunction "2_2") (pintype "passive"))
      (node (ref "C70") (pin "2") (pinfunction "2_2") (pintype "passive"))
      (node (ref "C8") (pin "2") (pinfunction "2_2") (pintype "passive"))
      (node (ref "C9") (pin "2") (pinfunction "2_2") (pintype "passive"))
      (node (ref "C91") (pin "1") (pinfunction "1_1") (pintype "passive"))
      (node (ref "C92") (pin "1") (pinfunction "1_1") (pintype "passive"))
      (node (ref "J96") (pin "4") (pinfunction "4_4") (pintype "passive"))
      (node (ref "L1") (pin "2") (pinfunction "2_2") (pintype "passive"))
      (node (ref "R14") (pin "2") (pinfunction "2_2") (pintype "passive"))
      (node (ref "R15") (pin "1") (pinfunction "1_1") (pintype "passive"))
      (node (ref "R17") (pin "1") (pinfunction "1_1") (pintype "passive"))
      (node (ref "R18") (pin "1") (pinfunction "1_1") (pintype "passive"))
      (node (ref "R19") (pin "1") (pinfunction "1_1") (pintype "passive"))
      (node (ref "R20") (pin "2") (pinfunction "2_2") (pintype "passive"))
      (node (ref "R21") (pin "2") (pinfunction "2_2") (pintype "passive"))
      (node (ref "R22") (pin "1") (pinfunction "1_1") (pintype "passive"))
      (node (ref "R23") (pin "2") (pinfunction "2_2") (pintype "passive"))
      (node (ref "R24") (pin "1") (pinfunction "1_1") (pintype "passive"))
      (node (ref "R250") (pin "2") (pinfunction "2_2") (pintype "passive"))
      (node (ref "U1") (pin "114") (pinfunction "VDIOM_114") (pintype "bidirectional"))
      (node (ref "U1") (pin "13") (pinfunction "VDIOP0_13") (pintype "bidirectional"))
      (node (ref "U1") (pin "132") (pinfunction "VDIOM_132") (pintype "bidirectional"))
      (node (ref "U1") (pin "169") (pinfunction "VDIOP1_169") (pintype "bidirectional"))
      (node (ref "U1") (pin "187") (pinfunction "VDIOP0_187") (pintype "bidirectional"))
      (node (ref "U1") (pin "199") (pinfunction "VDIOP0_199") (pintype "bidirectional"))
      (node (ref "U1") (pin "24") (pinfunction "VDIOP0_24") (pintype "bidirectional"))
      (node (ref "U1") (pin "32") (pinfunction "VDIOP0_32") (pintype "bidirectional"))
      (node (ref "U1") (pin "5") (pinfunction "VDIOP0_5") (pintype "bidirectional"))
      (node (ref "U1") (pin "52") (pinfunction "VDIOP0_52") (pintype "bidirectional"))
      (node (ref "U1") (pin "65") (pinfunction "VDIOM_65") (pintype "bidirectional"))
      (node (ref "U1") (pin "90") (pinfunction "VDIOM_90") (pintype "bidirectional"))
      (node (ref "U10") (pin "12") (pinfunction "VCC_12") (pintype "bidirectional"))
      (node (ref "U10") (pin "37") (pinfunction "VCC_37") (pintype "bidirectional"))
      (node (ref "U11") (pin "6") (pinfunction "VCC_6") (pintype "power_in"))
      (node (ref "U20") (pin "16") (pinfunction "VCC_16") (pintype "power_in"))
      (node (ref "U23") (pin "3") (pinfunction "OUT_3") (pintype "power_in"))
      (node (ref "U24") (pin "3") (pinfunction "IN_3") (pintype "power_in"))
      (node (ref "U50") (pin "10") (pinfunction "VDD33_10") (pintype "power_in"))
      (node (ref "U50") (pin "15") (pinfunction "VDD33_15") (pintype "power_in"))
      (node (ref "U50") (pin "23") (pinfunction "VDD33_23") (pintype "power_in"))
      (node (ref "U50") (pin "26") (pinfunction "RESET_N_26") (pintype "input"))
      (node (ref "U50") (pin "27") (pinfunction "VBUS_DET_27") (pintype "passive"))
      (node (ref "U50") (pin "29") (pinfunction "VDD33_29") (pintype "power_in"))
      (node (ref "U50") (pin "36") (pinfunction "VDD33_36") (pintype "passive"))
      (node (ref "U50") (pin "5") (pinfunction "VDD33_5") (pintype "power_in"))
      (node (ref "U7") (pin "1") (pinfunction "VDD_1") (pintype "power_in"))
      (node (ref "U7") (pin "14") (pinfunction "VDD_14") (pintype "power_in"))
      (node (ref "U7") (pin "27") (pinfunction "VDD_27") (pintype "power_in"))
      (node (ref "U7") (pin "3") (pinfunction "VDDQ_3") (pintype "power_in"))
      (node (ref "U7") (pin "43") (pinfunction "VDDQ_43") (pintype "power_in"))
      (node (ref "U7") (pin "49") (pinfunction "VDDQ_49") (pintype "power_in"))
      (node (ref "U7") (pin "9") (pinfunction "VDDQ_9") (pintype "power_in"))
      (node (ref "U8") (pin "1") (pinfunction "VDD_1") (pintype "power_in"))
      (node (ref "U8") (pin "14") (pinfunction "VDD_14") (pintype "power_in"))
      (node (ref "U8") (pin "27") (pinfunction "VDD_27") (pintype "power_in"))
      (node (ref "U8") (pin "3") (pinfunction "VDDQ_3") (pintype "power_in"))
      (node (ref "U8") (pin "43") (pinfunction "VDDQ_43") (pintype "power_in"))
      (node (ref "U8") (pin "49") (pinfunction "VDDQ_49") (pintype "power_in"))
      (node (ref "U8") (pin "9") (pinfunction "VDDQ_9") (pintype "power_in"))
    )
    (net (code "63") (name "5V") (class "Default")
      (node (ref "C45") (pin "1") (pinfunction "1_1") (pintype "passive"))
      (node (ref "C80") (pin "1") (pinfunction "1_1") (pintype "passive"))
      (node (ref "C81") (pin "1") (pinfunction "1_1") (pintype "passive"))
      (node (ref "C82") (pin "1") (pinfunction "1_1") (pintype "passive"))
      (node (ref "C83") (pin "1") (pinfunction "1_1") (pintype "passive"))
      (node (ref "J51") (pin "1") (pinfunction "VBUS_1") (pintype "power_in"))
      (node (ref "J51") (pin "5") (pinfunction "VBUS_5") (pintype "power_in"))
      (node (ref "J52") (pin "1") (pinfunction "VBUS_1") (pintype "power_in"))
      (node (ref "J52") (pin "5") (pinfunction "VBUS_5") (pintype "power_in"))
      (node (ref "P20") (pin "2") (pinfunction "2_2") (pintype "passive"))
      (node (ref "U23") (pin "1") (pinfunction "IN_1") (pintype "power_in"))
    )
    (net (code "64") (name "GND") (class "Default")
      (node (ref "C1") (pin "1") (pinfunction "1_1") (pintype "passive"))
      (node (ref "C10") (pin "1") (pinfunction "1_1") (pintype "passive"))
      (node (ref "C11") (pin "1") (pinfunction "1_1") (pintype "passive"))
      (node (ref "C12") (pin "1") (pinfunction "1_1") (pintype "passive"))
      (node (ref "C120") (pin "2") (pinfunction "2_2") (pintype "passive"))
      (node (ref "C121") (pin "1") (pinfunction "1_1") (pintype "passive"))
      (node (ref "C13") (pin "1") (pinfunction "1_1") (pintype "passive"))
      (node (ref "C14") (pin "1") (pinfunction "1_1") (pintype "passive"))
      (node (ref "C15") (pin "1") (pinfunction "1_1") (pintype "passive"))
      (node (ref "C16") (pin "1") (pinfunction "1_1") (pintype "passive"))
      (node (ref "C17") (pin "1") (pinfunction "1_1") (pintype "passive"))
      (node (ref "C18") (pin "1") (pinfunction "1_1") (pintype "passive"))
      (node (ref "C19") (pin "1") (pinfunction "1_1") (pintype "passive"))
      (node (ref "C2") (pin "1") (pinfunction "1_1") (pintype "passive"))
      (node (ref "C20") (pin "1") (pinfunction "1_1") (pintype "passive"))
      (node (ref "C21") (pin "2") (pinfunction "2_2") (pintype "passive"))
      (node (ref "C22") (pin "2") (pinfunction "2_2") (pintype "passive"))
      (node (ref "C23") (pin "2") (pinfunction "2_2") (pintype "passive"))
      (node (ref "C24") (pin "2") (pinfunction "2_2") (pintype "passive"))
      (node (ref "C25") (pin "1") (pinfunction "1_1") (pintype "passive"))
      (node (ref "C26") (pin "2") (pinfunction "2_2") (pintype "passive"))
      (node (ref "C27") (pin "2") (pinfunction "2_2") (pintype "passive"))
      (node (ref "C28") (pin "2") (pinfunction "2_2") (pintype "passive"))
      (node (ref "C29") (pin "2") (pinfunction "2_2") (pintype "passive"))
      (node (ref "C3") (pin "1") (pinfunction "1_1") (pintype "passive"))
      (node (ref "C33") (pin "2") (pinfunction "2_2") (pintype "passive"))
      (node (ref "C34") (pin "2") (pinfunction "2_2") (pintype "passive"))
      (node (ref "C35") (pin "2") (pinfunction "2_2") (pintype "passive"))
      (node (ref "C38") (pin "1") (pinfunction "1_1") (pintype "passive"))
      (node (ref "C39") (pin "2") (pinfunction "2_2") (pintype "passive"))
      (node (ref "C4") (pin "1") (pinfunction "1_1") (pintype "passive"))
      (node (ref "C40") (pin "2") (pinfunction "2_2") (pintype "passive"))
      (node (ref "C41") (pin "2") (pinfunction "2_2") (pintype "passive"))
      (node (ref "C42") (pin "1") (pinfunction "1_1") (pintype "passive"))
      (node (ref "C45") (pin "2") (pinfunction "2_2") (pintype "passive"))
      (node (ref "C46") (pin "2") (pinfunction "2_2") (pintype "passive"))
      (node (ref "C47") (pin "2") (pinfunction "2_2") (pintype "passive"))
      (node (ref "C5") (pin "1") (pinfunction "1_1") (pintype "passive"))
      (node (ref "C51") (pin "1") (pinfunction "1_1") (pintype "passive"))
      (node (ref "C52") (pin "1") (pinfunction "1_1") (pintype "passive"))
      (node (ref "C53") (pin "1") (pinfunction "1_1") (pintype "passive"))
      (node (ref "C54") (pin "1") (pinfunction "1_1") (pintype "passive"))
      (node (ref "C55") (pin "1") (pinfunction "1_1") (pintype "passive"))
      (node (ref "C56") (pin "1") (pinfunction "1_1") (pintype "passive"))
      (node (ref "C57") (pin "1") (pinfunction "1_1") (pintype "passive"))
      (node (ref "C58") (pin "1") (pinfunction "1_1") (pintype "passive"))
      (node (ref "C6") (pin "1") (pinfunction "1_1") (pintype "passive"))
      (node (ref "C60") (pin "2") (pinfunction "2_2") (pintype "passive"))
      (node (ref "C61") (pin "2") (pinfunction "2_2") (pintype "passive"))
      (node (ref "C62") (pin "2") (pinfunction "2_2") (pintype "passive"))
      (node (ref "C63") (pin "2") (pinfunction "2_2") (pintype "passive"))
      (node (ref "C64") (pin "2") (pinfunction "2_2") (pintype "passive"))
      (node (ref "C66") (pin "2") (pinfunction "2_2") (pintype "passive"))
      (node (ref "C7") (pin "1") (pinfunction "1_1") (pintype "passive"))
      (node (ref "C70") (pin "1") (pinfunction "1_1") (pintype "passive"))
      (node (ref "C8") (pin "1") (pinfunction "1_1") (pintype "passive"))
      (node (ref "C80") (pin "2") (pinfunction "2_2") (pintype "passive"))
      (node (ref "C81") (pin "2") (pinfunction "2_2") (pintype "passive"))
      (node (ref "C82") (pin "2") (pinfunction "2_2") (pintype "passive"))
      (node (ref "C83") (pin "2") (pinfunction "2_2") (pintype "passive"))
      (node (ref "C88") (pin "2") (pinfunction "2_2") (pintype "passive"))
      (node (ref "C89") (pin "2") (pinfunction "2_2") (pintype "passive"))
      (node (ref "C9") (pin "1") (pinfunction "1_1") (pintype "passive"))
      (node (ref "C90") (pin "2") (pinfunction "2_2") (pintype "passive"))
      (node (ref "C91") (pin "2") (pinfunction "2_2") (pintype "passive"))
      (node (ref "C92") (pin "2") (pinfunction "2_2") (pintype "passive"))
      (node (ref "C93") (pin "2") (pinfunction "2_2") (pintype "passive"))
      (node (ref "C98") (pin "2") (pinfunction "2_2") (pintype "passive"))
      (node (ref "C99") (pin "2") (pinfunction "2_2") (pintype "passive"))
      (node (ref "J2") (pin "4") (pinfunction "GND_4") (pintype "power_in"))
      (node (ref "J3") (pin "5") (pinfunction "5_5") (pintype "passive"))
      (node (ref "J51") (pin "4") (pinfunction "GND_4") (pintype "power_in"))
      (node (ref "J51") (pin "8") (pinfunction "GND_8") (pintype "power_in"))
      (node (ref "J52") (pin "4") (pinfunction "GND_4") (pintype "power_in"))
      (node (ref "J52") (pin "8") (pinfunction "GND_8") (pintype "power_in"))
      (node (ref "J7") (pin "2") (pinfunction "C2_2") (pintype "passive"))
      (node (ref "J9") (pin "1") (pinfunction "1_1") (pintype "passive"))
      (node (ref "J96") (pin "6") (pinfunction "6_6") (pintype "passive"))
      (node (ref "P20") (pin "1") (pinfunction "1_1") (pintype "passive"))
      (node (ref "R100") (pin "2") (pinfunction "2_2") (pintype "passive"))
      (node (ref "R13") (pin "2") (pinfunction "2_2") (pintype "passive"))
      (node (ref "R16") (pin "1") (pinfunction "1_1") (pintype "passive"))
      (node (ref "R88") (pin "2") (pinfunction "2_2") (pintype "passive"))
      (node (ref "R89") (pin "1") (pinfunction "1_1") (pintype "passive"))
      (node (ref "R90") (pin "2") (pinfunction "2_2") (pintype "passive"))
      (node (ref "R91") (pin "2") (pinfunction "2_2") (pintype "passive"))
      (node (ref "R92") (pin "2") (pinfunction "2_2") (pintype "passive"))
      (node (ref "R93") (pin "2") (pinfunction "2_2") (pintype "passive"))
      (node (ref "R94") (pin "1") (pinfunction "1_1") (pintype "passive"))
      (node (ref "R95") (pin "1") (pinfunction "1_1") (pintype "passive"))
      (node (ref "S1") (pin "1") (pinfunction "1_1") (pintype "passive"))
      (node (ref "S2") (pin "2") (pinfunction "2_2") (pintype "passive"))
      (node (ref "U1") (pin "113") (pinfunction "GND_113") (pintype "bidirectional"))
      (node (ref "U1") (pin "133") (pinfunction "GND_133") (pintype "bidirectional"))
      (node (ref "U1") (pin "14") (pinfunction "GND_14") (pintype "bidirectional"))
      (node (ref "U1") (pin "146") (pinfunction "GND_146") (pintype "bidirectional"))
      (node (ref "U1") (pin "151") (pinfunction "GNDPLL_151") (pintype "bidirectional"))
      (node (ref "U1") (pin "153") (pinfunction "GNDPLL_153") (pintype "bidirectional"))
      (node (ref "U1") (pin "156") (pinfunction "GNDANA_156") (pintype "bidirectional"))
      (node (ref "U1") (pin "170") (pinfunction "GND_170") (pintype "bidirectional"))
      (node (ref "U1") (pin "173") (pinfunction "GND_173") (pintype "bidirectional"))
      (node (ref "U1") (pin "188") (pinfunction "GND_188") (pintype "bidirectional"))
      (node (ref "U1") (pin "200") (pinfunction "GND_200") (pintype "bidirectional"))
      (node (ref "U1") (pin "204") (pinfunction "GND_204") (pintype "bidirectional"))
      (node (ref "U1") (pin "25") (pinfunction "GND_25") (pintype "bidirectional"))
      (node (ref "U1") (pin "33") (pinfunction "GND_33") (pintype "bidirectional"))
      (node (ref "U1") (pin "39") (pinfunction "GND_39") (pintype "bidirectional"))
      (node (ref "U1") (pin "44") (pinfunction "GNDBU_44") (pintype "bidirectional"))
      (node (ref "U1") (pin "53") (pinfunction "GND_53") (pintype "bidirectional"))
      (node (ref "U1") (pin "6") (pinfunction "GND_6") (pintype "bidirectional"))
      (node (ref "U1") (pin "66") (pinfunction "GND_66") (pintype "bidirectional"))
      (node (ref "U1") (pin "78") (pinfunction "GND_78") (pintype "bidirectional"))
      (node (ref "U1") (pin "91") (pinfunction "GND_91") (pintype "bidirectional"))
      (node (ref "U10") (pin "13") (pinfunction "VSS_13") (pintype "bidirectional"))
      (node (ref "U10") (pin "36") (pinfunction "VSS_36") (pintype "bidirectional"))
      (node (ref "U10") (pin "38") (pinfunction "PRE_38") (pintype "bidirectional"))
      (node (ref "U11") (pin "7") (pinfunction "GND_7") (pintype "bidirectional"))
      (node (ref "U20") (pin "15") (pinfunction "GND_15") (pintype "power_in"))
      (node (ref "U23") (pin "4") (pinfunction "GND_4") (pintype "power_in"))
      (node (ref "U24") (pin "1") (pinfunction "GND_1") (pintype "power_in"))
      (node (ref "U50") (pin "11") (pinfunction "TEST_11") (pintype "passive"))
      (node (ref "U50") (pin "22") (pinfunction "NON_REM1_22") (pintype "passive"))
      (node (ref "U50") (pin "24") (pinfunction "CFG_SEL0_24") (pintype "passive"))
      (node (ref "U50") (pin "25") (pinfunction "CFG_SEL1_25") (pintype "passive"))
      (node (ref "U50") (pin "28") (pinfunction "NON_REM0_28") (pintype "passive"))
      (node (ref "U7") (pin "12") (pinfunction "VSSQ_12") (pintype "power_in"))
      (node (ref "U7") (pin "28") (pinfunction "VSS_28") (pintype "power_in"))
      (node (ref "U7") (pin "41") (pinfunction "VSS_41") (pintype "power_in"))
      (node (ref "U7") (pin "46") (pinfunction "VSSQ_46") (pintype "power_in"))
      (node (ref "U7") (pin "52") (pinfunction "VSSQ_52") (pintype "power_in"))
      (node (ref "U7") (pin "54") (pinfunction "VSS_54") (pintype "power_in"))
      (node (ref "U7") (pin "6") (pinfunction "VSSQ_6") (pintype "power_in"))
      (node (ref "U8") (pin "12") (pinfunction "VSSQ_12") (pintype "power_in"))
      (node (ref "U8") (pin "28") (pinfunction "VSS_28") (pintype "power_in"))
      (node (ref "U8") (pin "41") (pinfunction "VSS_41") (pintype "power_in"))
      (node (ref "U8") (pin "46") (pinfunction "VSSQ_46") (pintype "power_in"))
      (node (ref "U8") (pin "52") (pinfunction "VSSQ_52") (pintype "power_in"))
      (node (ref "U8") (pin "54") (pinfunction "VSS_54") (pintype "power_in"))
      (node (ref "U8") (pin "6") (pinfunction "VSSQ_6") (pintype "power_in"))
    )
    (net (code "65") (name "Net-(C29-Pad1)") (class "Default")
      (node (ref "C29") (pin "1") (pinfunction "1_1") (pintype "passive"))
      (node (ref "R3") (pin "2") (pinfunction "2_2") (pintype "passive"))
    )
    (net (code "66") (name "Net-(J2-D+)") (class "Default")
      (node (ref "J2") (pin "3") (pinfunction "D+_3") (pintype "input"))
      (node (ref "R11") (pin "2") (pinfunction "2_2") (pintype "passive"))
    )
    (net (code "67") (name "Net-(J2-D-)") (class "Default")
      (node (ref "J2") (pin "2") (pinfunction "D-_2") (pintype "input"))
      (node (ref "R10") (pin "2") (pinfunction "2_2") (pintype "passive"))
    )
    (net (code "68") (name "Net-(J7-C1)") (class "Default")
      (node (ref "J7") (pin "1") (pinfunction "C1_1") (pintype "passive"))
      (node (ref "R17") (pin "2") (pinfunction "2_2") (pintype "passive"))
      (node (ref "U1") (pin "40") (pinfunction "BMS_40") (pintype "bidirectional"))
    )
    (net (code "69") (name "Net-(J9-Pad2)") (class "Default")
      (node (ref "J9") (pin "2") (pinfunction "2_2") (pintype "passive"))
      (node (ref "R1") (pin "1") (pinfunction "1_1") (pintype "passive"))
    )
    (net (code "70") (name "Net-(J20-C2)") (class "Default")
      (node (ref "J20") (pin "2") (pinfunction "C2_2") (pintype "passive"))
      (node (ref "R24") (pin "2") (pinfunction "2_2") (pintype "passive"))
      (node (ref "U11") (pin "4") (pinfunction "CS_4") (pintype "input"))
    )
    (net (code "71") (name "Net-(J21-C1)") (class "Default")
      (node (ref "J21") (pin "1") (pinfunction "C1_1") (pintype "passive"))
      (node (ref "U1") (pin "59") (pinfunction "IRQ2/NCS3_NANDCS/PC14_59") (pintype "bidirectional"))
    )
    (net (code "72") (name "Net-(J21-C2)") (class "Default")
      (node (ref "J21") (pin "2") (pinfunction "C2_2") (pintype "passive"))
      (node (ref "R20") (pin "1") (pinfunction "1_1") (pintype "passive"))
      (node (ref "U10") (pin "9") (pinfunction "CE_9") (pintype "bidirectional"))
    )
    (net (code "73") (name "Net-(J51A-D+)") (class "Default")
      (node (ref "J51") (pin "3") (pinfunction "D+_3") (pintype "input"))
      (node (ref "R80") (pin "2") (pinfunction "2_2") (pintype "passive"))
      (node (ref "R88") (pin "1") (pinfunction "1_1") (pintype "passive"))
    )
    (net (code "74") (name "Net-(J51A-D-)") (class "Default")
      (node (ref "J51") (pin "2") (pinfunction "D-_2") (pintype "input"))
      (node (ref "R81") (pin "2") (pinfunction "2_2") (pintype "passive"))
      (node (ref "R89") (pin "2") (pinfunction "2_2") (pintype "passive"))
    )
    (net (code "75") (name "Net-(J51B-D+)") (class "Default")
      (node (ref "J51") (pin "7") (pinfunction "D+_7") (pintype "input"))
      (node (ref "R82") (pin "2") (pinfunction "2_2") (pintype "passive"))
      (node (ref "R91") (pin "1") (pinfunction "1_1") (pintype "passive"))
    )
    (net (code "76") (name "Net-(J51B-D-)") (class "Default")
      (node (ref "J51") (pin "6") (pinfunction "D-_6") (pintype "input"))
      (node (ref "R83") (pin "2") (pinfunction "2_2") (pintype "passive"))
      (node (ref "R90") (pin "1") (pinfunction "1_1") (pintype "passive"))
    )
    (net (code "77") (name "Net-(J52A-D+)") (class "Default")
      (node (ref "J52") (pin "3") (pinfunction "D+_3") (pintype "input"))
      (node (ref "R85") (pin "2") (pinfunction "2_2") (pintype "passive"))
      (node (ref "R92") (pin "1") (pinfunction "1_1") (pintype "passive"))
    )
    (net (code "78") (name "Net-(J52A-D-)") (class "Default")
      (node (ref "J52") (pin "2") (pinfunction "D-_2") (pintype "input"))
      (node (ref "R84") (pin "2") (pinfunction "2_2") (pintype "passive"))
      (node (ref "R93") (pin "1") (pinfunction "1_1") (pintype "passive"))
    )
    (net (code "79") (name "Net-(J52B-D+)") (class "Default")
      (node (ref "J52") (pin "7") (pinfunction "D+_7") (pintype "input"))
      (node (ref "R87") (pin "2") (pinfunction "2_2") (pintype "passive"))
      (node (ref "R94") (pin "2") (pinfunction "2_2") (pintype "passive"))
    )
    (net (code "80") (name "Net-(J52B-D-)") (class "Default")
      (node (ref "J52") (pin "6") (pinfunction "D-_6") (pintype "input"))
      (node (ref "R86") (pin "2") (pinfunction "2_2") (pintype "passive"))
      (node (ref "R95") (pin "2") (pinfunction "2_2") (pintype "passive"))
    )
    (net (code "81") (name "Net-(U1A-ADVREF)") (class "Default")
      (node (ref "C19") (pin "2") (pinfunction "2_2") (pintype "passive"))
      (node (ref "C20") (pin "2") (pinfunction "2_2") (pintype "passive"))
      (node (ref "C88") (pin "1") (pinfunction "1_1") (pintype "passive"))
      (node (ref "L1") (pin "1") (pinfunction "1_1") (pintype "passive"))
      (node (ref "U1") (pin "157") (pinfunction "ADVREF_157") (pintype "bidirectional"))
      (node (ref "U1") (pin "160") (pinfunction "VDDANA_160") (pintype "bidirectional"))
    )
    (net (code "82") (name "Net-(U1A-BA0{slash}A16)") (class "Default")
      (node (ref "U1") (pin "81") (pinfunction "BA0/A16_81") (pintype "bidirectional"))
      (node (ref "U7") (pin "20") (pinfunction "BA0_20") (pintype "input"))
      (node (ref "U8") (pin "20") (pinfunction "BA0_20") (pintype "input"))
    )
    (net (code "83") (name "Net-(U1A-BA1{slash}A17)") (class "Default")
      (node (ref "U1") (pin "80") (pinfunction "BA1/A17_80") (pintype "bidirectional"))
      (node (ref "U7") (pin "21") (pinfunction "BA1_21") (pintype "input"))
      (node (ref "U8") (pin "21") (pinfunction "BA1_21") (pintype "input"))
    )
    (net (code "84") (name "Net-(U1A-CAS)") (class "Default")
      (node (ref "U1") (pin "104") (pinfunction "CAS_104") (pintype "bidirectional"))
      (node (ref "U7") (pin "17") (pinfunction "~{CAS}_17") (pintype "input"))
      (node (ref "U8") (pin "17") (pinfunction "~{CAS}_17") (pintype "input"))
    )
    (net (code "85") (name "Net-(U1A-CFIOR{slash}NBS1{slash}NWR1)") (class "Default")
      (node (ref "U1") (pin "102") (pinfunction "CFIOR/NBS1/NWR1_102") (pintype "bidirectional"))
      (node (ref "U8") (pin "39") (pinfunction "DQMH_39") (pintype "input"))
    )
    (net (code "86") (name "Net-(U1A-CFIOW{slash}NBS3{slash}NWR3)") (class "Default")
      (node (ref "U1") (pin "101") (pinfunction "CFIOW/NBS3/NWR3_101") (pintype "bidirectional"))
      (node (ref "U7") (pin "39") (pinfunction "DQMH_39") (pintype "input"))
    )
    (net (code "87") (name "Net-(U1A-DDM)") (class "Default")
      (node (ref "C34") (pin "1") (pinfunction "1_1") (pintype "passive"))
      (node (ref "R10") (pin "1") (pinfunction "1_1") (pintype "passive"))
      (node (ref "U1") (pin "54") (pinfunction "DDM_54") (pintype "bidirectional"))
    )
    (net (code "88") (name "Net-(U1A-DDP)") (class "Default")
      (node (ref "C35") (pin "1") (pinfunction "1_1") (pintype "passive"))
      (node (ref "R11") (pin "1") (pinfunction "1_1") (pintype "passive"))
      (node (ref "U1") (pin "55") (pinfunction "DDP_55") (pintype "bidirectional"))
    )
    (net (code "89") (name "Net-(U1A-DRXD{slash}PB14)") (class "Default")
      (node (ref "P22") (pin "11") (pinfunction "11_11") (pintype "passive"))
      (node (ref "U1") (pin "21") (pinfunction "DRXD/PB14_21") (pintype "bidirectional"))
    )
    (net (code "90") (name "Net-(U1A-DTXD{slash}PB15)") (class "Default")
      (node (ref "P22") (pin "9") (pinfunction "9_9") (pintype "passive"))
      (node (ref "U1") (pin "22") (pinfunction "DTXD/PB15_22") (pintype "bidirectional"))
    )
    (net (code "91") (name "Net-(U1A-HDMA)") (class "Default")
      (node (ref "U1") (pin "50") (pinfunction "HDMA_50") (pintype "bidirectional"))
      (node (ref "U50") (pin "30") (pinfunction "USBDM_UP_30") (pintype "power_in"))
    )
    (net (code "92") (name "Net-(U1A-HDPA)") (class "Default")
      (node (ref "U1") (pin "51") (pinfunction "HDPA_51") (pintype "bidirectional"))
      (node (ref "U50") (pin "31") (pinfunction "USBDP_UP_31") (pintype "input"))
    )
    (net (code "93") (name "Net-(U1A-NBS0{slash}A0)") (class "Default")
      (node (ref "U1") (pin "99") (pinfunction "NBS0/A0_99") (pintype "bidirectional"))
      (node (ref "U8") (pin "15") (pinfunction "DQML_15") (pintype "input"))
    )
    (net (code "94") (name "Net-(U1A-NWR2{slash}NBS2{slash}A1)") (class "Default")
      (node (ref "U1") (pin "98") (pinfunction "NWR2/NBS2/A1_98") (pintype "bidirectional"))
      (node (ref "U7") (pin "15") (pinfunction "DQML_15") (pintype "input"))
    )
    (net (code "95") (name "Net-(U1A-OSCSEL)") (class "Default")
      (node (ref "R1") (pin "2") (pinfunction "2_2") (pintype "passive"))
      (node (ref "U1") (pin "41") (pinfunction "OSCSEL_41") (pintype "bidirectional"))
    )
    (net (code "96") (name "Net-(U1A-PLLRCA)") (class "Default")
      (node (ref "C28") (pin "1") (pinfunction "1_1") (pintype "passive"))
      (node (ref "R3") (pin "1") (pinfunction "1_1") (pintype "passive"))
      (node (ref "U1") (pin "154") (pinfunction "PLLRCA_154") (pintype "bidirectional"))
    )
    (net (code "97") (name "Net-(U1A-RAS)") (class "Default")
      (node (ref "U1") (pin "105") (pinfunction "RAS_105") (pintype "bidirectional"))
      (node (ref "U7") (pin "18") (pinfunction "~{RAS}_18") (pintype "input"))
      (node (ref "U8") (pin "18") (pinfunction "~{RAS}_18") (pintype "input"))
    )
    (net (code "98") (name "Net-(U1A-RXD0{slash}{slash}PB5)") (class "Default")
      (node (ref "P22") (pin "3") (pinfunction "3_3") (pintype "passive"))
      (node (ref "U1") (pin "16") (pinfunction "RXD0//PB5_16") (pintype "bidirectional"))
    )
    (net (code "99") (name "Net-(U1A-SDA10)") (class "Default")
      (node (ref "U1") (pin "100") (pinfunction "SDA10_100") (pintype "bidirectional"))
      (node (ref "U7") (pin "22") (pinfunction "A10_22") (pintype "input"))
      (node (ref "U8") (pin "22") (pinfunction "A10_22") (pintype "input"))
    )
    (net (code "100") (name "Net-(U1A-SDCK)") (class "Default")
      (node (ref "U1") (pin "115") (pinfunction "SDCK_115") (pintype "bidirectional"))
      (node (ref "U7") (pin "38") (pinfunction "CLK_38") (pintype "input"))
      (node (ref "U8") (pin "38") (pinfunction "CLK_38") (pintype "input"))
    )
    (net (code "101") (name "Net-(U1A-SDCKE)") (class "Default")
      (node (ref "U1") (pin "117") (pinfunction "SDCKE_117") (pintype "bidirectional"))
      (node (ref "U7") (pin "37") (pinfunction "CKE_37") (pintype "input"))
      (node (ref "U8") (pin "37") (pinfunction "CKE_37") (pintype "input"))
    )
    (net (code "102") (name "Net-(U1A-SDCS{slash}NCS1)") (class "Default")
      (node (ref "R18") (pin "2") (pinfunction "2_2") (pintype "passive"))
      (node (ref "R19") (pin "2") (pinfunction "2_2") (pintype "passive"))
      (node (ref "U1") (pin "103") (pinfunction "SDCS/NCS1_103") (pintype "bidirectional"))
      (node (ref "U7") (pin "19") (pinfunction "~{CS}_19") (pintype "input"))
      (node (ref "U8") (pin "19") (pinfunction "~{CS}_19") (pintype "input"))
    )
    (net (code "103") (name "Net-(U1A-SDWE)") (class "Default")
      (node (ref "U1") (pin "116") (pinfunction "SDWE_116") (pintype "bidirectional"))
      (node (ref "U7") (pin "16") (pinfunction "~{WE}_16") (pintype "input"))
      (node (ref "U8") (pin "16") (pinfunction "~{WE}_16") (pintype "input"))
    )
    (net (code "104") (name "Net-(U1A-TCLK1{slash}TXD1{slash}PB6)") (class "Default")
      (node (ref "P22") (pin "5") (pinfunction "5_5") (pintype "passive"))
      (node (ref "U1") (pin "17") (pinfunction "TCLK1/TXD1/PB6_17") (pintype "bidirectional"))
    )
    (net (code "105") (name "Net-(U1A-TCLK2{slash}RXD1{slash}PB7)") (class "Default")
      (node (ref "P22") (pin "7") (pinfunction "7_7") (pintype "passive"))
      (node (ref "U1") (pin "18") (pinfunction "TCLK2/RXD1/PB7_18") (pintype "bidirectional"))
    )
    (net (code "106") (name "Net-(U1A-TST)") (class "Default")
      (node (ref "R16") (pin "2") (pinfunction "2_2") (pintype "passive"))
      (node (ref "U1") (pin "42") (pinfunction "TST_42") (pintype "bidirectional"))
    )
    (net (code "107") (name "Net-(U1A-TXD0{slash}PB4)") (class "Default")
      (node (ref "P22") (pin "1") (pinfunction "1_1") (pintype "passive"))
      (node (ref "U1") (pin "15") (pinfunction "TXD0/PB4_15") (pintype "bidirectional"))
    )
    (net (code "108") (name "Net-(U1A-WKUP)") (class "Default")
      (node (ref "R2") (pin "1") (pinfunction "1_1") (pintype "passive"))
      (node (ref "S1") (pin "2") (pinfunction "2_2") (pintype "passive"))
      (node (ref "U1") (pin "48") (pinfunction "WKUP_48") (pintype "bidirectional"))
    )
    (net (code "109") (name "Net-(U1A-XIN)") (class "Default")
      (node (ref "C22") (pin "1") (pinfunction "1_1") (pintype "passive"))
      (node (ref "U1") (pin "149") (pinfunction "XIN_149") (pintype "bidirectional"))
      (node (ref "Y1") (pin "1") (pinfunction "OSC1_1") (pintype "passive"))
    )
    (net (code "110") (name "Net-(U1A-XIN32)") (class "Default")
      (node (ref "C24") (pin "1") (pinfunction "1_1") (pintype "passive"))
      (node (ref "U1") (pin "46") (pinfunction "XIN32_46") (pintype "bidirectional"))
      (node (ref "Y2") (pin "1") (pinfunction "OSC1_1") (pintype "passive"))
    )
    (net (code "111") (name "Net-(U1A-XOUT)") (class "Default")
      (node (ref "C21") (pin "1") (pinfunction "1_1") (pintype "passive"))
      (node (ref "U1") (pin "150") (pinfunction "XOUT_150") (pintype "bidirectional"))
      (node (ref "Y1") (pin "2") (pinfunction "OSC2_2") (pintype "passive"))
    )
    (net (code "112") (name "Net-(U1A-XOUT32)") (class "Default")
      (node (ref "C23") (pin "1") (pinfunction "1_1") (pintype "passive"))
      (node (ref "U1") (pin "45") (pinfunction "XOUT32_45") (pintype "bidirectional"))
      (node (ref "Y2") (pin "2") (pinfunction "OSC2_2") (pintype "passive"))
    )
    (net (code "113") (name "Net-(U10-R{slash}B)") (class "Default")
      (node (ref "R21") (pin "1") (pinfunction "1_1") (pintype "passive"))
      (node (ref "U1") (pin "56") (pinfunction "NCS6/FIQ/PC13_56") (pintype "bidirectional"))
      (node (ref "U10") (pin "7") (pinfunction "R/B_7") (pintype "bidirectional"))
    )
    (net (code "114") (name "Net-(U10-WP)") (class "Default")
      (node (ref "R22") (pin "2") (pinfunction "2_2") (pintype "passive"))
      (node (ref "U10") (pin "19") (pinfunction "WP_19") (pintype "bidirectional"))
    )
    (net (code "115") (name "Net-(U20-C1+)") (class "Default")
      (node (ref "C37") (pin "2") (pinfunction "2_2") (pintype "passive"))
      (node (ref "U20") (pin "1") (pinfunction "C1+_1") (pintype "passive"))
    )
    (net (code "116") (name "Net-(U20-C1-)") (class "Default")
      (node (ref "C37") (pin "1") (pinfunction "1_1") (pintype "passive"))
      (node (ref "U20") (pin "3") (pinfunction "C1-_3") (pintype "passive"))
    )
    (net (code "117") (name "Net-(U20-C2+)") (class "Default")
      (node (ref "C36") (pin "2") (pinfunction "2_2") (pintype "passive"))
      (node (ref "U20") (pin "4") (pinfunction "C2+_4") (pintype "passive"))
    )
    (net (code "118") (name "Net-(U20-C2-)") (class "Default")
      (node (ref "C36") (pin "1") (pinfunction "1_1") (pintype "passive"))
      (node (ref "U20") (pin "5") (pinfunction "C2-_5") (pintype "passive"))
    )
    (net (code "119") (name "Net-(U20-R1IN)") (class "Default")
      (node (ref "J3") (pin "2") (pinfunction "2_2") (pintype "passive"))
      (node (ref "U20") (pin "13") (pinfunction "R1IN_13") (pintype "input"))
    )
    (net (code "120") (name "Net-(U20-R1OUT)") (class "Default")
      (node (ref "P22") (pin "12") (pinfunction "12_12") (pintype "passive"))
      (node (ref "P22") (pin "4") (pinfunction "4_4") (pintype "passive"))
      (node (ref "P22") (pin "8") (pinfunction "8_8") (pintype "passive"))
      (node (ref "U20") (pin "12") (pinfunction "R1OUT_12") (pintype "output"))
    )
    (net (code "121") (name "Net-(U20-T2IN)") (class "Default")
      (node (ref "P22") (pin "10") (pinfunction "10_10") (pintype "passive"))
      (node (ref "P22") (pin "2") (pinfunction "2_2") (pintype "passive"))
      (node (ref "P22") (pin "6") (pinfunction "6_6") (pintype "passive"))
      (node (ref "R14") (pin "1") (pinfunction "1_1") (pintype "passive"))
      (node (ref "U20") (pin "10") (pinfunction "T2IN_10") (pintype "input"))
    )
    (net (code "122") (name "Net-(U20-T2OUT)") (class "Default")
      (node (ref "J3") (pin "3") (pinfunction "3_3") (pintype "passive"))
      (node (ref "U20") (pin "7") (pinfunction "T2OUT_7") (pintype "output"))
    )
    (net (code "123") (name "Net-(U20-V+)") (class "Default")
      (node (ref "C38") (pin "2") (pinfunction "2_2") (pintype "passive"))
      (node (ref "U20") (pin "2") (pinfunction "V+_2") (pintype "power_in"))
    )
    (net (code "124") (name "Net-(U20-V-)") (class "Default")
      (node (ref "C42") (pin "2") (pinfunction "2_2") (pintype "passive"))
      (node (ref "U20") (pin "6") (pinfunction "V-_6") (pintype "power_in"))
    )
    (net (code "125") (name "Net-(U50-CRTFILT)") (class "Default")
      (node (ref "C98") (pin "1") (pinfunction "1_1") (pintype "passive"))
      (node (ref "U50") (pin "14") (pinfunction "CRTFILT_14") (pintype "passive"))
    )
    (net (code "126") (name "Net-(U50-OCSN1)") (class "Default")
      (node (ref "R250") (pin "1") (pinfunction "1_1") (pintype "passive"))
      (node (ref "U50") (pin "13") (pinfunction "OCSN1_13") (pintype "output"))
      (node (ref "U50") (pin "17") (pinfunction "OCSN2_17") (pintype "output"))
      (node (ref "U50") (pin "19") (pinfunction "OCSN3_19") (pintype "output"))
      (node (ref "U50") (pin "21") (pinfunction "OCSN4_21") (pintype "output"))
    )
    (net (code "127") (name "Net-(U50-PLLFILT)") (class "Default")
      (node (ref "C99") (pin "1") (pinfunction "1_1") (pintype "passive"))
      (node (ref "U50") (pin "34") (pinfunction "PLLFILT_34") (pintype "passive"))
    )
    (net (code "128") (name "Net-(U50-RBIAS)") (class "Default")
      (node (ref "R100") (pin "1") (pinfunction "1_1") (pintype "passive"))
      (node (ref "U50") (pin "35") (pinfunction "RBIAS_35") (pintype "passive"))
    )
    (net (code "129") (name "Net-(U50-USB_DM1)") (class "Default")
      (node (ref "R81") (pin "1") (pinfunction "1_1") (pintype "passive"))
      (node (ref "U50") (pin "1") (pinfunction "USB_DM1_1") (pintype "bidirectional"))
    )
    (net (code "130") (name "Net-(U50-USB_DM2)") (class "Default")
      (node (ref "R83") (pin "1") (pinfunction "1_1") (pintype "passive"))
      (node (ref "U50") (pin "3") (pinfunction "USB_DM2_3") (pintype "bidirectional"))
    )
    (net (code "131") (name "Net-(U50-USB_DM3)") (class "Default")
      (node (ref "R84") (pin "1") (pinfunction "1_1") (pintype "passive"))
      (node (ref "U50") (pin "6") (pinfunction "USB_DM3_6") (pintype "bidirectional"))
    )
    (net (code "132") (name "Net-(U50-USB_DM4)") (class "Default")
      (node (ref "R86") (pin "1") (pinfunction "1_1") (pintype "passive"))
      (node (ref "U50") (pin "8") (pinfunction "USB_DM4_8") (pintype "bidirectional"))
    )
    (net (code "133") (name "Net-(U50-USB_DP1)") (class "Default")
      (node (ref "R80") (pin "1") (pinfunction "1_1") (pintype "passive"))
      (node (ref "U50") (pin "2") (pinfunction "USB_DP1_2") (pintype "bidirectional"))
    )
    (net (code "134") (name "Net-(U50-USB_DP2)") (class "Default")
      (node (ref "R82") (pin "1") (pinfunction "1_1") (pintype "passive"))
      (node (ref "U50") (pin "4") (pinfunction "USB_DP2_4") (pintype "bidirectional"))
    )
    (net (code "135") (name "Net-(U50-USB_DP3)") (class "Default")
      (node (ref "R85") (pin "1") (pinfunction "1_1") (pintype "passive"))
      (node (ref "U50") (pin "7") (pinfunction "USB_DP3_7") (pintype "bidirectional"))
    )
    (net (code "136") (name "Net-(U50-USB_DP4)") (class "Default")
      (node (ref "R87") (pin "1") (pinfunction "1_1") (pintype "passive"))
      (node (ref "U50") (pin "9") (pinfunction "USB_DP4_9") (pintype "bidirectional"))
    )
    (net (code "137") (name "Net-(U50-XTALIN)") (class "Default")
      (node (ref "C90") (pin "1") (pinfunction "1_1") (pintype "passive"))
      (node (ref "R105") (pin "1") (pinfunction "1_1") (pintype "passive"))
      (node (ref "U50") (pin "33") (pinfunction "XTALIN_33") (pintype "passive"))
      (node (ref "Y3") (pin "1") (pinfunction "OSC1_1") (pintype "passive"))
    )
    (net (code "138") (name "Net-(U50-XTAL_OUT)") (class "Default")
      (node (ref "C89") (pin "1") (pinfunction "1_1") (pintype "passive"))
      (node (ref "R105") (pin "2") (pinfunction "2_2") (pintype "passive"))
      (node (ref "U50") (pin "32") (pinfunction "XTAL_OUT_32") (pintype "passive"))
      (node (ref "Y3") (pin "2") (pinfunction "OSC2_2") (pintype "passive"))
    )
    (net (code "139") (name "unconnected-(J2-SHLD-Pad5)") (class "Default")
      (node (ref "J2") (pin "5") (pinfunction "SHLD_5") (pintype "passive"))
    )
    (net (code "140") (name "unconnected-(J2-SHLD-Pad6)") (class "Default")
      (node (ref "J2") (pin "6") (pinfunction "SHLD_6") (pintype "passive"))
    )
    (net (code "141") (name "unconnected-(J3-MH1-Pad10)") (class "Default")
      (node (ref "J3") (pin "10") (pinfunction "MH1_10") (pintype "passive"))
    )
    (net (code "142") (name "unconnected-(J3-MH2-Pad11)") (class "Default")
      (node (ref "J3") (pin "11") (pinfunction "MH2_11") (pintype "passive"))
    )
    (net (code "143") (name "unconnected-(J3-Pad1)") (class "Default")
      (node (ref "J3") (pin "1") (pinfunction "1_1") (pintype "passive"))
    )
    (net (code "144") (name "unconnected-(J3-Pad4)") (class "Default")
      (node (ref "J3") (pin "4") (pinfunction "4_4") (pintype "passive"))
    )
    (net (code "145") (name "unconnected-(J3-Pad6)") (class "Default")
      (node (ref "J3") (pin "6") (pinfunction "6_6") (pintype "passive"))
    )
    (net (code "146") (name "unconnected-(J3-Pad7)") (class "Default")
      (node (ref "J3") (pin "7") (pinfunction "7_7") (pintype "passive"))
    )
    (net (code "147") (name "unconnected-(J3-Pad8)") (class "Default")
      (node (ref "J3") (pin "8") (pinfunction "8_8") (pintype "passive"))
    )
    (net (code "148") (name "unconnected-(J3-Pad9)") (class "Default")
      (node (ref "J3") (pin "9") (pinfunction "9_9") (pintype "passive"))
    )
    (net (code "149") (name "unconnected-(J96-PadMH1)") (class "Default")
      (node (ref "J96") (pin "MH1") (pinfunction "MH1_MH1") (pintype "passive"))
    )
    (net (code "150") (name "unconnected-(J96-PadMH2)") (class "Default")
      (node (ref "J96") (pin "MH2") (pinfunction "MH2_MH2") (pintype "passive"))
    )
    (net (code "151") (name "unconnected-(J96-PadSW2)") (class "Default")
      (node (ref "J96") (pin "SW2") (pinfunction "SW2_SW2") (pintype "passive"))
    )
    (net (code "152") (name "unconnected-(J96-PadSW3)") (class "Default")
      (node (ref "J96") (pin "SW3") (pinfunction "SW3_SW3") (pintype "passive"))
    )
    (net (code "153") (name "unconnected-(U1A-A12-Pad85)") (class "Default")
      (node (ref "U1") (pin "85") (pinfunction "A12_85") (pintype "bidirectional"))
    )
    (net (code "154") (name "unconnected-(U1A-A15-Pad82)") (class "Default")
      (node (ref "U1") (pin "82") (pinfunction "A15_82") (pintype "bidirectional"))
    )
    (net (code "155") (name "unconnected-(U1A-A18-Pad79)") (class "Default")
      (node (ref "U1") (pin "79") (pinfunction "A18_79") (pintype "bidirectional"))
    )
    (net (code "156") (name "unconnected-(U1A-A19-Pad76)") (class "Default")
      (node (ref "U1") (pin "76") (pinfunction "A19_76") (pintype "bidirectional"))
    )
    (net (code "157") (name "unconnected-(U1A-A20-Pad75)") (class "Default")
      (node (ref "U1") (pin "75") (pinfunction "A20_75") (pintype "bidirectional"))
    )
    (net (code "158") (name "unconnected-(U1A-CFCE1{slash}TIOB2{slash}PC6-Pad63)") (class "Default")
      (node (ref "U1") (pin "63") (pinfunction "CFCE1/TIOB2/PC6_63") (pintype "bidirectional"))
    )
    (net (code "159") (name "unconnected-(U1A-CFCE2{slash}TIOB1{slash}PC7-Pad64)") (class "Default")
      (node (ref "U1") (pin "64") (pinfunction "CFCE2/TIOB1/PC7_64") (pintype "bidirectional"))
    )
    (net (code "160") (name "unconnected-(U1A-CFOE{slash}NRD-Pad69)") (class "Default")
      (node (ref "U1") (pin "69") (pinfunction "CFOE/NRD_69") (pintype "bidirectional"))
    )
    (net (code "161") (name "unconnected-(U1A-CFWE{slash}NWE{slash}NWR0-Pad70)") (class "Default")
      (node (ref "U1") (pin "70") (pinfunction "CFWE/NWE/NWR0_70") (pintype "bidirectional"))
    )
    (net (code "162") (name "unconnected-(U1A-CTS3{slash}A25_CFRNW{slash}PC10-Pad58)") (class "Default")
      (node (ref "U1") (pin "58") (pinfunction "CTS3/A25_CFRNW/PC10_58") (pintype "bidirectional"))
    )
    (net (code "163") (name "unconnected-(U1A-IRQ1{slash}NWAIT{slash}PC15-Pad127)") (class "Default")
      (node (ref "U1") (pin "127") (pinfunction "IRQ1/NWAIT/PC15_127") (pintype "bidirectional"))
    )
    (net (code "164") (name "unconnected-(U1A-ISI_D0{slash}RK0{slash}PB20-Pad163)") (class "Default")
      (node (ref "U1") (pin "163") (pinfunction "ISI_D0/RK0/PB20_163") (pintype "bidirectional"))
    )
    (net (code "165") (name "unconnected-(U1A-ISI_D1{slash}RF0{slash}PB21-Pad164)") (class "Default")
      (node (ref "U1") (pin "164") (pinfunction "ISI_D1/RF0/PB21_164") (pintype "bidirectional"))
    )
    (net (code "166") (name "unconnected-(U1A-ISI_D2{slash}DSR0{slash}PB22-Pad165)") (class "Default")
      (node (ref "U1") (pin "165") (pinfunction "ISI_D2/DSR0/PB22_165") (pintype "bidirectional"))
    )
    (net (code "167") (name "unconnected-(U1A-ISI_D3{slash}DCD0{slash}PB23-Pad166)") (class "Default")
      (node (ref "U1") (pin "166") (pinfunction "ISI_D3/DCD0/PB23_166") (pintype "bidirectional"))
    )
    (net (code "168") (name "unconnected-(U1A-ISI_D4{slash}DTR0{slash}PB24-Pad167)") (class "Default")
      (node (ref "U1") (pin "167") (pinfunction "ISI_D4/DTR0/PB24_167") (pintype "bidirectional"))
    )
    (net (code "169") (name "unconnected-(U1A-ISI_D5{slash}RI0{slash}PB25-Pad168)") (class "Default")
      (node (ref "U1") (pin "168") (pinfunction "ISI_D5/RI0/PB25_168") (pintype "bidirectional"))
    )
    (net (code "170") (name "unconnected-(U1A-ISI_D6{slash}RTS0{slash}PB26-Pad171)") (class "Default")
      (node (ref "U1") (pin "171") (pinfunction "ISI_D6/RTS0/PB26_171") (pintype "bidirectional"))
    )
    (net (code "171") (name "unconnected-(U1A-ISI_D7{slash}CTS0{slash}PB27-Pad172)") (class "Default")
      (node (ref "U1") (pin "172") (pinfunction "ISI_D7/CTS0/PB27_172") (pintype "bidirectional"))
    )
    (net (code "172") (name "unconnected-(U1A-ISI_D8{slash}TXD3{slash}PB10-Pad161)") (class "Default")
      (node (ref "U1") (pin "161") (pinfunction "ISI_D8/TXD3/PB10_161") (pintype "bidirectional"))
    )
    (net (code "173") (name "unconnected-(U1A-ISI_D9{slash}RXD3{slash}PB11-Pad162)") (class "Default")
      (node (ref "U1") (pin "162") (pinfunction "ISI_D9/RXD3/PB11_162") (pintype "bidirectional"))
    )
    (net (code "174") (name "unconnected-(U1A-ISI_HSYNC{slash}PCK0{slash}PB30-Pad177)") (class "Default")
      (node (ref "U1") (pin "177") (pinfunction "ISI_HSYNC/PCK0/PB30_177") (pintype "bidirectional"))
    )
    (net (code "175") (name "unconnected-(U1A-ISI_MCK{slash}PCK1{slash}PB31-Pad178)") (class "Default")
      (node (ref "U1") (pin "178") (pinfunction "ISI_MCK/PCK1/PB31_178") (pintype "bidirectional"))
    )
    (net (code "176") (name "unconnected-(U1A-ISI_PCK{slash}RTS1{slash}PB28-Pad175)") (class "Default")
      (node (ref "U1") (pin "175") (pinfunction "ISI_PCK/RTS1/PB28_175") (pintype "bidirectional"))
    )
    (net (code "177") (name "unconnected-(U1A-ISI_VSYNC{slash}CTS1{slash}PB29-Pad176)") (class "Default")
      (node (ref "U1") (pin "176") (pinfunction "ISI_VSYNC/CTS1/PB29_176") (pintype "bidirectional"))
    )
    (net (code "178") (name "unconnected-(U1A-JTAGSEL-Pad43)") (class "Default")
      (node (ref "U1") (pin "43") (pinfunction "JTAGSEL_43") (pintype "bidirectional"))
    )
    (net (code "179") (name "unconnected-(U1A-N.C-Pad152)") (class "Default")
      (node (ref "U1") (pin "152") (pinfunction "N.C_152") (pintype "bidirectional"))
    )
    (net (code "180") (name "unconnected-(U1A-NCS0-Pad68)") (class "Default")
      (node (ref "U1") (pin "68") (pinfunction "NCS0_68") (pintype "bidirectional"))
    )
    (net (code "181") (name "unconnected-(U1A-PA6{slash}MCDA0-Pad185)") (class "Default")
      (node (ref "U1") (pin "185") (pinfunction "PA6/MCDA0_185") (pintype "bidirectional"))
    )
    (net (code "182") (name "unconnected-(U1A-PA7{slash}MCCDA-Pad186)") (class "Default")
      (node (ref "U1") (pin "186") (pinfunction "PA7/MCCDA_186") (pintype "bidirectional"))
    )
    (net (code "183") (name "unconnected-(U1A-PA9{slash}MCDA1-Pad190)") (class "Default")
      (node (ref "U1") (pin "190") (pinfunction "PA9/MCDA1_190") (pintype "bidirectional"))
    )
    (net (code "184") (name "unconnected-(U1A-PA10{slash}MCDA2{slash}ETX2-Pad191)") (class "Default")
      (node (ref "U1") (pin "191") (pinfunction "PA10/MCDA2/ETX2_191") (pintype "bidirectional"))
    )
    (net (code "185") (name "unconnected-(U1A-PA11{slash}MCDA3{slash}ETX3-Pad192)") (class "Default")
      (node (ref "U1") (pin "192") (pinfunction "PA11/MCDA3/ETX3_192") (pintype "bidirectional"))
    )
    (net (code "186") (name "unconnected-(U1A-PA12{slash}ETX0-Pad193)") (class "Default")
      (node (ref "U1") (pin "193") (pinfunction "PA12/ETX0_193") (pintype "bidirectional"))
    )
    (net (code "187") (name "unconnected-(U1A-PA13{slash}ETX1-Pad194)") (class "Default")
      (node (ref "U1") (pin "194") (pinfunction "PA13/ETX1_194") (pintype "bidirectional"))
    )
    (net (code "188") (name "unconnected-(U1A-PA14{slash}ERX0-Pad195)") (class "Default")
      (node (ref "U1") (pin "195") (pinfunction "PA14/ERX0_195") (pintype "bidirectional"))
    )
    (net (code "189") (name "unconnected-(U1A-PA15{slash}ERX1-Pad196)") (class "Default")
      (node (ref "U1") (pin "196") (pinfunction "PA15/ERX1_196") (pintype "bidirectional"))
    )
    (net (code "190") (name "unconnected-(U1A-PA16{slash}ETXEN-Pad197)") (class "Default")
      (node (ref "U1") (pin "197") (pinfunction "PA16/ETXEN_197") (pintype "bidirectional"))
    )
    (net (code "191") (name "unconnected-(U1A-PA17{slash}ERXDV-Pad198)") (class "Default")
      (node (ref "U1") (pin "198") (pinfunction "PA17/ERXDV_198") (pintype "bidirectional"))
    )
    (net (code "192") (name "unconnected-(U1A-PA18{slash}ERXER-Pad201)") (class "Default")
      (node (ref "U1") (pin "201") (pinfunction "PA18/ERXER_201") (pintype "bidirectional"))
    )
    (net (code "193") (name "unconnected-(U1A-PA19{slash}ETXCK-Pad202)") (class "Default")
      (node (ref "U1") (pin "202") (pinfunction "PA19/ETXCK_202") (pintype "bidirectional"))
    )
    (net (code "194") (name "unconnected-(U1A-PA20{slash}EMDC-Pad205)") (class "Default")
      (node (ref "U1") (pin "205") (pinfunction "PA20/EMDC_205") (pintype "bidirectional"))
    )
    (net (code "195") (name "unconnected-(U1A-PA21{slash}EMDIO-Pad206)") (class "Default")
      (node (ref "U1") (pin "206") (pinfunction "PA21/EMDIO_206") (pintype "bidirectional"))
    )
    (net (code "196") (name "unconnected-(U1A-PA22{slash}ADTRG{slash}ETXER-Pad207)") (class "Default")
      (node (ref "U1") (pin "207") (pinfunction "PA22/ADTRG/ETXER_207") (pintype "bidirectional"))
    )
    (net (code "197") (name "unconnected-(U1A-PA23{slash}TWD{slash}ETX2-Pad208)") (class "Default")
      (node (ref "U1") (pin "208") (pinfunction "PA23/TWD/ETX2_208") (pintype "bidirectional"))
    )
    (net (code "198") (name "unconnected-(U1A-PA24{slash}TWCK{slash}ETX3-Pad1)") (class "Default")
      (node (ref "U1") (pin "1") (pinfunction "PA24/TWCK/ETX3_1") (pintype "bidirectional"))
    )
    (net (code "199") (name "unconnected-(U1A-PA25{slash}TCLK0{slash}ERX2-Pad2)") (class "Default")
      (node (ref "U1") (pin "2") (pinfunction "PA25/TCLK0/ERX2_2") (pintype "bidirectional"))
    )
    (net (code "200") (name "unconnected-(U1A-PA26{slash}TIOA0{slash}ERX3-Pad3)") (class "Default")
      (node (ref "U1") (pin "3") (pinfunction "PA26/TIOA0/ERX3_3") (pintype "bidirectional"))
    )
    (net (code "201") (name "unconnected-(U1A-PA27{slash}TIOA1{slash}ERXCK-Pad4)") (class "Default")
      (node (ref "U1") (pin "4") (pinfunction "PA27/TIOA1/ERXCK_4") (pintype "bidirectional"))
    )
    (net (code "202") (name "unconnected-(U1A-PA28{slash}TIOA2{slash}ECRS-Pad7)") (class "Default")
      (node (ref "U1") (pin "7") (pinfunction "PA28/TIOA2/ECRS_7") (pintype "bidirectional"))
    )
    (net (code "203") (name "unconnected-(U1A-PA29{slash}SCK1{slash}ECOL-Pad8)") (class "Default")
      (node (ref "U1") (pin "8") (pinfunction "PA29/SCK1/ECOL_8") (pintype "bidirectional"))
    )
    (net (code "204") (name "unconnected-(U1A-PCK0{slash}AD1{slash}PC1-Pad159)") (class "Default")
      (node (ref "U1") (pin "159") (pinfunction "PCK0/AD1/PC1_159") (pintype "bidirectional"))
    )
    (net (code "205") (name "unconnected-(U1A-RTCK-Pad37)") (class "Default")
      (node (ref "U1") (pin "37") (pinfunction "RTCK_37") (pintype "bidirectional"))
    )
    (net (code "206") (name "unconnected-(U1A-RTS3{slash}NCS4_CFCS0{slash}PC8-Pad61)") (class "Default")
      (node (ref "U1") (pin "61") (pinfunction "RTS3/NCS4_CFCS0/PC8_61") (pintype "bidirectional"))
    )
    (net (code "207") (name "unconnected-(U1A-RXD2{slash}PB9-Pad20)") (class "Default")
      (node (ref "U1") (pin "20") (pinfunction "RXD2/PB9_20") (pintype "bidirectional"))
    )
    (net (code "208") (name "unconnected-(U1A-SCK3{slash}AD0{slash}PC0-Pad158)") (class "Default")
      (node (ref "U1") (pin "158") (pinfunction "SCK3/AD0/PC0_158") (pintype "bidirectional"))
    )
    (net (code "209") (name "unconnected-(U1A-SPI1_NPCS2{slash}A23{slash}PC4-Pad62)") (class "Default")
      (node (ref "U1") (pin "62") (pinfunction "SPI1_NPCS2/A23/PC4_62") (pintype "bidirectional"))
    )
    (net (code "210") (name "unconnected-(U1A-TCK-Pad34)") (class "Default")
      (node (ref "U1") (pin "34") (pinfunction "TCK_34") (pintype "bidirectional"))
    )
    (net (code "211") (name "unconnected-(U1A-TCLK3{slash}TK0{slash}PB16-Pad23)") (class "Default")
      (node (ref "U1") (pin "23") (pinfunction "TCLK3/TK0/PB16_23") (pintype "bidirectional"))
    )
    (net (code "212") (name "unconnected-(U1A-TCLK4{slash}TF0{slash}PB17-Pad26)") (class "Default")
      (node (ref "U1") (pin "26") (pinfunction "TCLK4/TF0/PB17_26") (pintype "bidirectional"))
    )
    (net (code "213") (name "unconnected-(U1A-TDI-Pad30)") (class "Default")
      (node (ref "U1") (pin "30") (pinfunction "TDI_30") (pintype "bidirectional"))
    )
    (net (code "214") (name "unconnected-(U1A-TDO-Pad29)") (class "Default")
      (node (ref "U1") (pin "29") (pinfunction "TDO_29") (pintype "bidirectional"))
    )
    (net (code "215") (name "unconnected-(U1A-TIOA3{slash}SPI1_MISO{slash}PB0-Pad9)") (class "Default")
      (node (ref "U1") (pin "9") (pinfunction "TIOA3/SPI1_MISO/PB0_9") (pintype "bidirectional"))
    )
    (net (code "216") (name "unconnected-(U1A-TIOA4{slash}SPI1_SPCK{slash}PB2-Pad11)") (class "Default")
      (node (ref "U1") (pin "11") (pinfunction "TIOA4/SPI1_SPCK/PB2_11") (pintype "bidirectional"))
    )
    (net (code "217") (name "unconnected-(U1A-TIOA5{slash}SPI1_NPCS0{slash}PB3-Pad12)") (class "Default")
      (node (ref "U1") (pin "12") (pinfunction "TIOA5/SPI1_NPCS0/PB3_12") (pintype "bidirectional"))
    )
    (net (code "218") (name "unconnected-(U1A-TIOB0{slash}NCS5_CFCS1{slash}PC9-Pad60)") (class "Default")
      (node (ref "U1") (pin "60") (pinfunction "TIOB0/NCS5_CFCS1/PC9_60") (pintype "bidirectional"))
    )
    (net (code "219") (name "unconnected-(U1A-TIOB3{slash}SPI1_MOSI{slash}PB1-Pad10)") (class "Default")
      (node (ref "U1") (pin "10") (pinfunction "TIOB3/SPI1_MOSI/PB1_10") (pintype "bidirectional"))
    )
    (net (code "220") (name "unconnected-(U1A-TIOB4{slash}TD0{slash}PB18-Pad27)") (class "Default")
      (node (ref "U1") (pin "27") (pinfunction "TIOB4/TD0/PB18_27") (pintype "bidirectional"))
    )
    (net (code "221") (name "unconnected-(U1A-TIOB5{slash}RD0{slash}PB19-Pad28)") (class "Default")
      (node (ref "U1") (pin "28") (pinfunction "TIOB5/RD0/PB19_28") (pintype "bidirectional"))
    )
    (net (code "222") (name "unconnected-(U1A-TMS-Pad31)") (class "Default")
      (node (ref "U1") (pin "31") (pinfunction "TMS_31") (pintype "bidirectional"))
    )
    (net (code "223") (name "unconnected-(U1A-TXD2{slash}PB8-Pad19)") (class "Default")
      (node (ref "U1") (pin "19") (pinfunction "TXD2/PB8_19") (pintype "bidirectional"))
    )
    (net (code "224") (name "unconnected-(U7-NC-Pad40)") (class "Default")
      (node (ref "U7") (pin "40") (pinfunction "NC_40") (pintype "passive"))
    )
    (net (code "225") (name "unconnected-(U8-NC-Pad40)") (class "Default")
      (node (ref "U8") (pin "40") (pinfunction "NC_40") (pintype "passive"))
    )
    (net (code "226") (name "unconnected-(U10-N.C-Pad1)") (class "Default")
      (node (ref "U10") (pin "1") (pinfunction "N.C_1") (pintype "bidirectional"))
    )
    (net (code "227") (name "unconnected-(U10-N.C-Pad2)") (class "Default")
      (node (ref "U10") (pin "2") (pinfunction "N.C_2") (pintype "bidirectional"))
    )
    (net (code "228") (name "unconnected-(U10-N.C-Pad3)") (class "Default")
      (node (ref "U10") (pin "3") (pinfunction "N.C_3") (pintype "bidirectional"))
    )
    (net (code "229") (name "unconnected-(U10-N.C-Pad4)") (class "Default")
      (node (ref "U10") (pin "4") (pinfunction "N.C_4") (pintype "bidirectional"))
    )
    (net (code "230") (name "unconnected-(U10-N.C-Pad5)") (class "Default")
      (node (ref "U10") (pin "5") (pinfunction "N.C_5") (pintype "bidirectional"))
    )
    (net (code "231") (name "unconnected-(U10-N.C-Pad6)") (class "Default")
      (node (ref "U10") (pin "6") (pinfunction "N.C_6") (pintype "bidirectional"))
    )
    (net (code "232") (name "unconnected-(U10-N.C-Pad10)") (class "Default")
      (node (ref "U10") (pin "10") (pinfunction "N.C_10") (pintype "bidirectional"))
    )
    (net (code "233") (name "unconnected-(U10-N.C-Pad11)") (class "Default")
      (node (ref "U10") (pin "11") (pinfunction "N.C_11") (pintype "bidirectional"))
    )
    (net (code "234") (name "unconnected-(U10-N.C-Pad14)") (class "Default")
      (node (ref "U10") (pin "14") (pinfunction "N.C_14") (pintype "bidirectional"))
    )
    (net (code "235") (name "unconnected-(U10-N.C-Pad15)") (class "Default")
      (node (ref "U10") (pin "15") (pinfunction "N.C_15") (pintype "bidirectional"))
    )
    (net (code "236") (name "unconnected-(U10-N.C-Pad20)") (class "Default")
      (node (ref "U10") (pin "20") (pinfunction "N.C_20") (pintype "bidirectional"))
    )
    (net (code "237") (name "unconnected-(U10-N.C-Pad21)") (class "Default")
      (node (ref "U10") (pin "21") (pinfunction "N.C_21") (pintype "bidirectional"))
    )
    (net (code "238") (name "unconnected-(U10-N.C-Pad22)") (class "Default")
      (node (ref "U10") (pin "22") (pinfunction "N.C_22") (pintype "bidirectional"))
    )
    (net (code "239") (name "unconnected-(U10-N.C-Pad23)") (class "Default")
      (node (ref "U10") (pin "23") (pinfunction "N.C_23") (pintype "bidirectional"))
    )
    (net (code "240") (name "unconnected-(U10-N.C-Pad24)") (class "Default")
      (node (ref "U10") (pin "24") (pinfunction "N.C_24") (pintype "bidirectional"))
    )
    (net (code "241") (name "unconnected-(U10-N.C-Pad25)") (class "Default")
      (node (ref "U10") (pin "25") (pinfunction "N.C_25") (pintype "bidirectional"))
    )
    (net (code "242") (name "unconnected-(U10-N.C-Pad26)") (class "Default")
      (node (ref "U10") (pin "26") (pinfunction "N.C_26") (pintype "bidirectional"))
    )
    (net (code "243") (name "unconnected-(U10-N.C-Pad27)") (class "Default")
      (node (ref "U10") (pin "27") (pinfunction "N.C_27") (pintype "bidirectional"))
    )
    (net (code "244") (name "unconnected-(U10-N.C-Pad28)") (class "Default")
      (node (ref "U10") (pin "28") (pinfunction "N.C_28") (pintype "bidirectional"))
    )
    (net (code "245") (name "unconnected-(U10-N.C-Pad33)") (class "Default")
      (node (ref "U10") (pin "33") (pinfunction "N.C_33") (pintype "bidirectional"))
    )
    (net (code "246") (name "unconnected-(U10-N.C-Pad34)") (class "Default")
      (node (ref "U10") (pin "34") (pinfunction "N.C_34") (pintype "bidirectional"))
    )
    (net (code "247") (name "unconnected-(U10-N.C-Pad35)") (class "Default")
      (node (ref "U10") (pin "35") (pinfunction "N.C_35") (pintype "bidirectional"))
    )
    (net (code "248") (name "unconnected-(U10-N.C-Pad39)") (class "Default")
      (node (ref "U10") (pin "39") (pinfunction "N.C_39") (pintype "bidirectional"))
    )
    (net (code "249") (name "unconnected-(U10-N.C-Pad40)") (class "Default")
      (node (ref "U10") (pin "40") (pinfunction "N.C_40") (pintype "bidirectional"))
    )
    (net (code "250") (name "unconnected-(U10-N.C-Pad45)") (class "Default")
      (node (ref "U10") (pin "45") (pinfunction "N.C_45") (pintype "bidirectional"))
    )
    (net (code "251") (name "unconnected-(U10-N.C-Pad46)") (class "Default")
      (node (ref "U10") (pin "46") (pinfunction "N.C_46") (pintype "bidirectional"))
    )
    (net (code "252") (name "unconnected-(U10-N.C-Pad47)") (class "Default")
      (node (ref "U10") (pin "47") (pinfunction "N.C_47") (pintype "bidirectional"))
    )
    (net (code "253") (name "unconnected-(U10-N.C-Pad48)") (class "Default")
      (node (ref "U10") (pin "48") (pinfunction "N.C_48") (pintype "bidirectional"))
    )
    (net (code "254") (name "unconnected-(U11-WP-Pad5)") (class "Default")
      (node (ref "U11") (pin "5") (pinfunction "WP_5") (pintype "bidirectional"))
    )
    (net (code "255") (name "unconnected-(U20-R2IN-Pad8)") (class "Default")
      (node (ref "U20") (pin "8") (pinfunction "R2IN_8") (pintype "input"))
    )
    (net (code "256") (name "unconnected-(U20-R2OUT-Pad9)") (class "Default")
      (node (ref "U20") (pin "9") (pinfunction "R2OUT_9") (pintype "output"))
    )
    (net (code "257") (name "unconnected-(U20-T1IN-Pad11)") (class "Default")
      (node (ref "U20") (pin "11") (pinfunction "T1IN_11") (pintype "input"))
    )
    (net (code "258") (name "unconnected-(U20-T1OUT-Pad14)") (class "Default")
      (node (ref "U20") (pin "14") (pinfunction "T1OUT_14") (pintype "output"))
    )
    (net (code "259") (name "unconnected-(U50-GND_PAD-Pad37)") (class "Default")
      (node (ref "U50") (pin "37") (pinfunction "GND_PAD_37") (pintype "power_in"))
    )
    (net (code "260") (name "unconnected-(U50-PRTPWR1-Pad12)") (class "Default")
      (node (ref "U50") (pin "12") (pinfunction "PRTPWR1_12") (pintype "output"))
    )
    (net (code "261") (name "unconnected-(U50-PRTPWR2-Pad16)") (class "Default")
      (node (ref "U50") (pin "16") (pinfunction "PRTPWR2_16") (pintype "output"))
    )
    (net (code "262") (name "unconnected-(U50-PRTPWR3-Pad18)") (class "Default")
      (node (ref "U50") (pin "18") (pinfunction "PRTPWR3_18") (pintype "output"))
    )
    (net (code "263") (name "unconnected-(U50-PTRPWR4-Pad20)") (class "Default")
      (node (ref "U50") (pin "20") (pinfunction "PTRPWR4_20") (pintype "output"))
    )
  )
)
